# Emech_DevBoard_v2_0.net
KiCad netlist of a schematic drawn in EAGLE
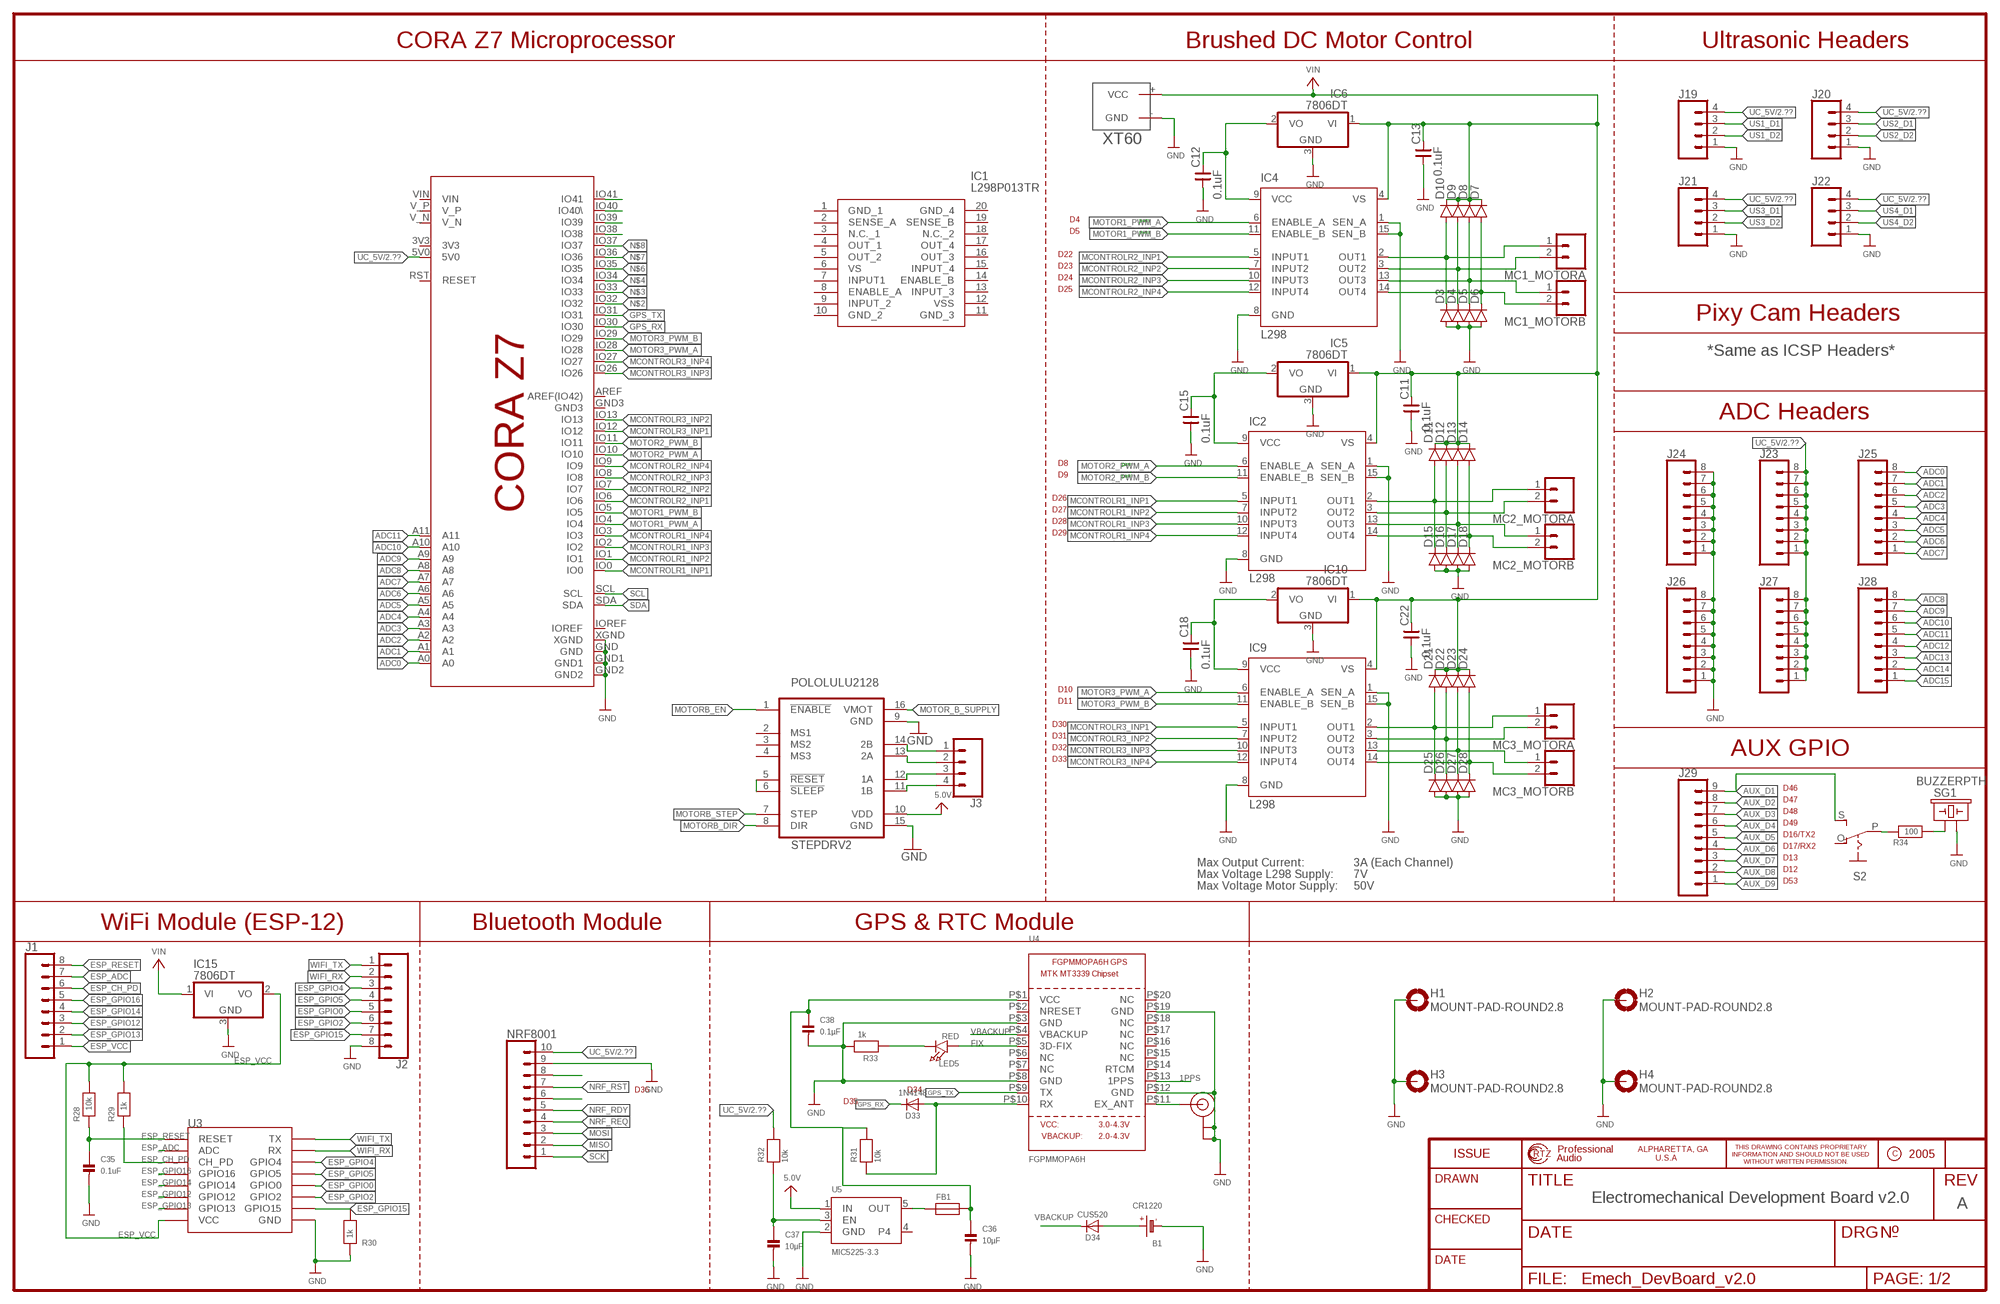
[diagram p0: schematic, sheet 1]
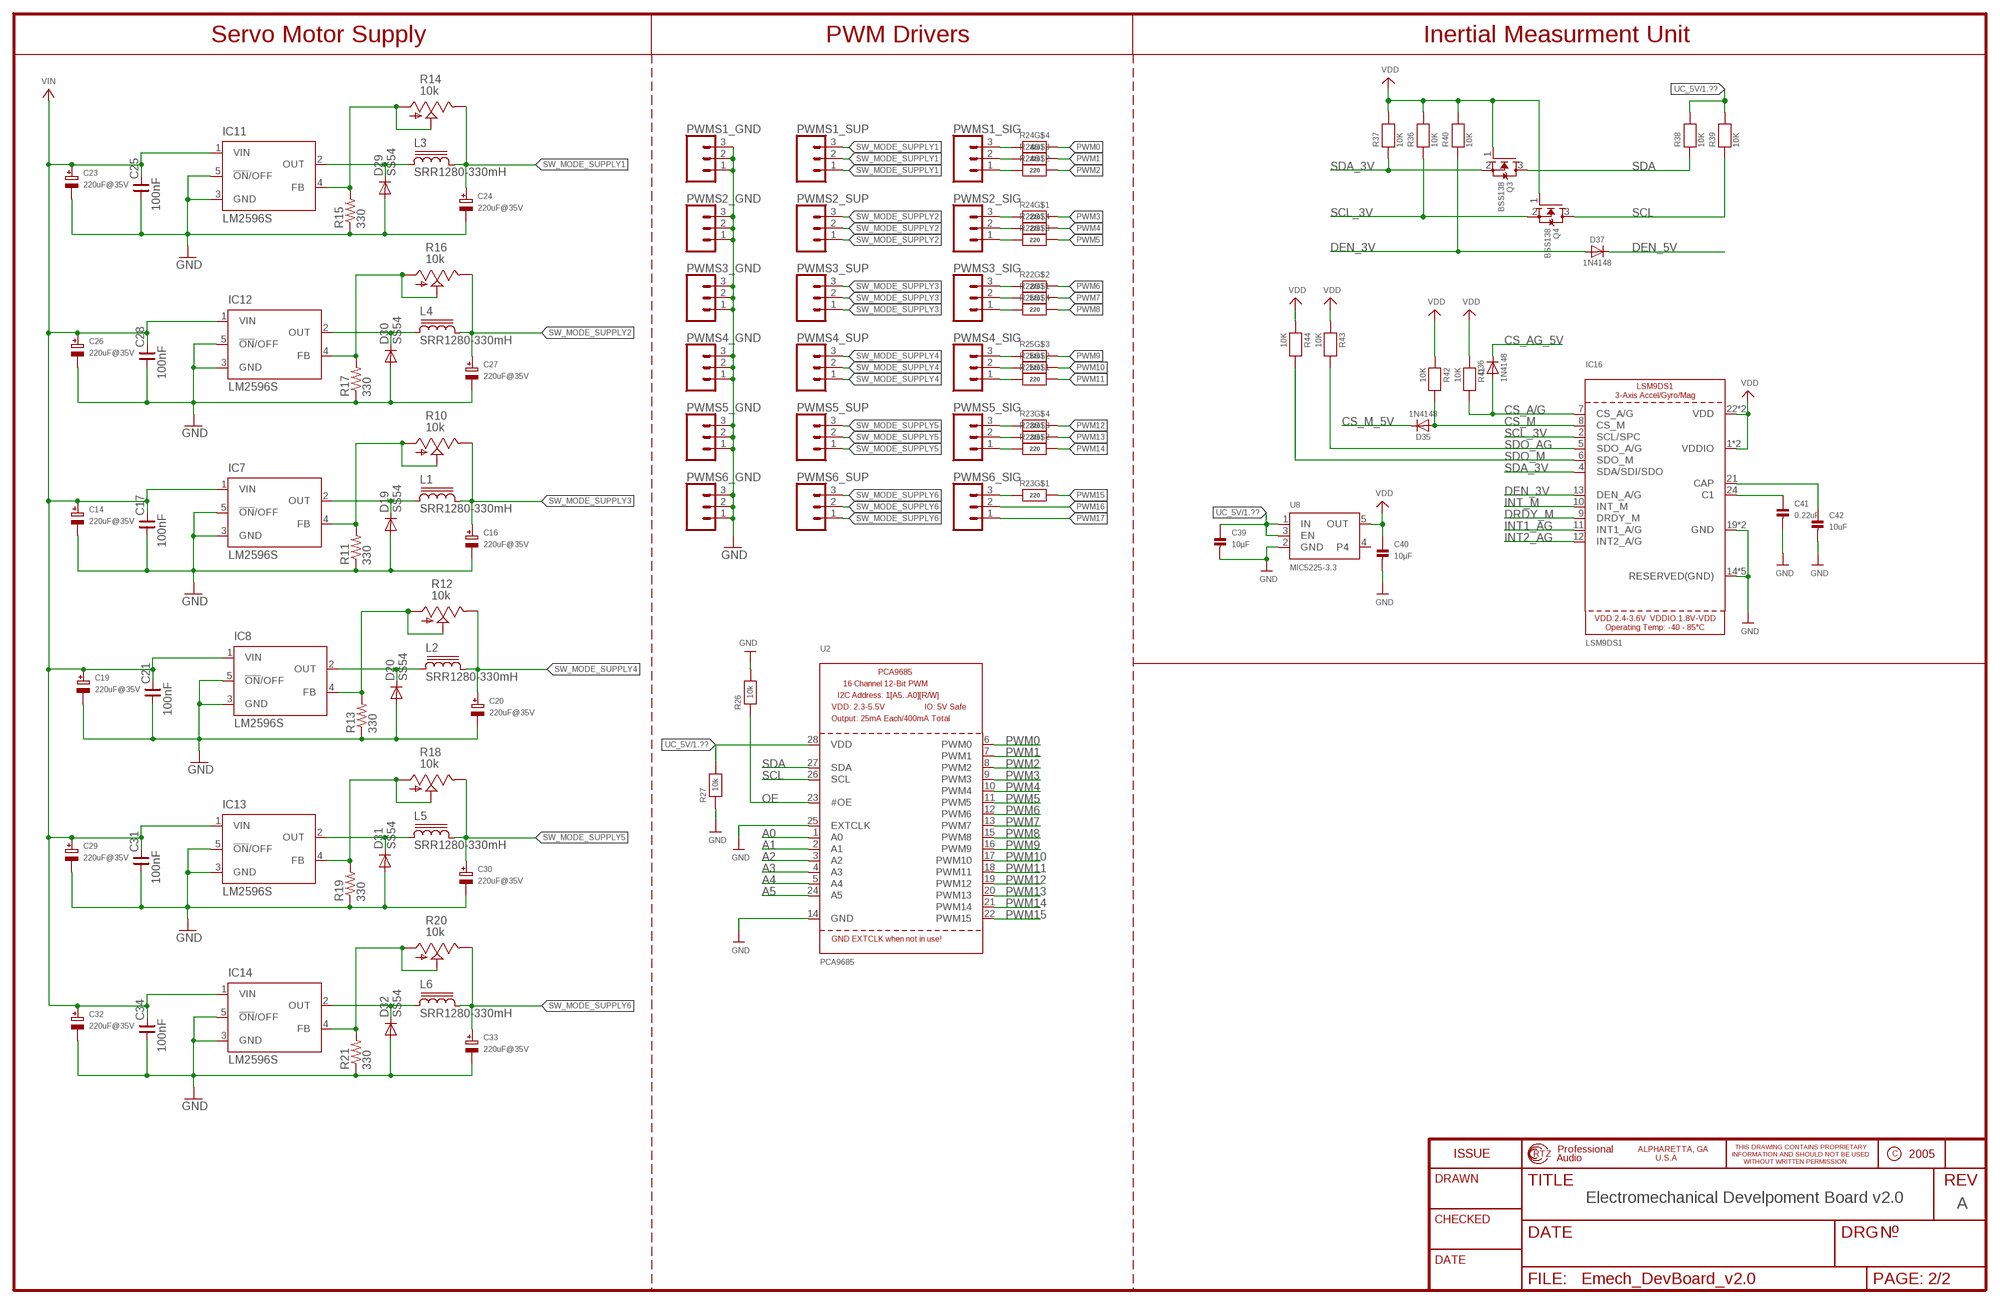
[diagram p1: schematic, sheet 2]

(export (version "E")
  (design (tool "Eeschema 10.0.6"))
  (components
    (comp (ref "C14")
      (value "220uF@35V")
      (footprint "eagle-import:PANASONIC_D")
      (libsource (lib "eagle-import") (part "CAP_ELECTROLYTICPANASONIC_D"))
    )
    (comp (ref "C16")
      (value "220uF@35V")
      (footprint "eagle-import:PANASONIC_D")
      (libsource (lib "eagle-import") (part "CAP_ELECTROLYTICPANASONIC_D"))
    )
    (comp (ref "C17")
      (value "100nF")
      (footprint "eagle-import:0603")
      (libsource (lib "eagle-import") (part "CNP-0603"))
    )
    (comp (ref "C19")
      (value "220uF@35V")
      (footprint "eagle-import:PANASONIC_D")
      (libsource (lib "eagle-import") (part "CAP_ELECTROLYTICPANASONIC_D"))
    )
    (comp (ref "C20")
      (value "220uF@35V")
      (footprint "eagle-import:PANASONIC_D")
      (libsource (lib "eagle-import") (part "CAP_ELECTROLYTICPANASONIC_D"))
    )
    (comp (ref "C21")
      (value "100nF")
      (footprint "eagle-import:0603")
      (libsource (lib "eagle-import") (part "CNP-0603"))
    )
    (comp (ref "C23")
      (value "220uF@35V")
      (footprint "eagle-import:PANASONIC_D")
      (libsource (lib "eagle-import") (part "CAP_ELECTROLYTICPANASONIC_D"))
    )
    (comp (ref "C24")
      (value "220uF@35V")
      (footprint "eagle-import:PANASONIC_D")
      (libsource (lib "eagle-import") (part "CAP_ELECTROLYTICPANASONIC_D"))
    )
    (comp (ref "C25")
      (value "100nF")
      (footprint "eagle-import:0603")
      (libsource (lib "eagle-import") (part "CNP-0603"))
    )
    (comp (ref "C26")
      (value "220uF@35V")
      (footprint "eagle-import:PANASONIC_D")
      (libsource (lib "eagle-import") (part "CAP_ELECTROLYTICPANASONIC_D"))
    )
    (comp (ref "C27")
      (value "220uF@35V")
      (footprint "eagle-import:PANASONIC_D")
      (libsource (lib "eagle-import") (part "CAP_ELECTROLYTICPANASONIC_D"))
    )
    (comp (ref "C28")
      (value "100nF")
      (footprint "eagle-import:0603")
      (libsource (lib "eagle-import") (part "CNP-0603"))
    )
    (comp (ref "C29")
      (value "220uF@35V")
      (footprint "eagle-import:PANASONIC_D")
      (libsource (lib "eagle-import") (part "CAP_ELECTROLYTICPANASONIC_D"))
    )
    (comp (ref "C30")
      (value "220uF@35V")
      (footprint "eagle-import:PANASONIC_D")
      (libsource (lib "eagle-import") (part "CAP_ELECTROLYTICPANASONIC_D"))
    )
    (comp (ref "C31")
      (value "100nF")
      (footprint "eagle-import:0603")
      (libsource (lib "eagle-import") (part "CNP-0603"))
    )
    (comp (ref "C32")
      (value "220uF@35V")
      (footprint "eagle-import:PANASONIC_D")
      (libsource (lib "eagle-import") (part "CAP_ELECTROLYTICPANASONIC_D"))
    )
    (comp (ref "C33")
      (value "220uF@35V")
      (footprint "eagle-import:PANASONIC_D")
      (libsource (lib "eagle-import") (part "CAP_ELECTROLYTICPANASONIC_D"))
    )
    (comp (ref "C34")
      (value "100nF")
      (footprint "eagle-import:0603")
      (libsource (lib "eagle-import") (part "CNP-0603"))
    )
    (comp (ref "C39")
      (value "10µF")
      (footprint "eagle-import:0603")
      (libsource (lib "eagle-import") (part "CAP_CERAMIC0603"))
    )
    (comp (ref "C40")
      (value "10µF")
      (footprint "eagle-import:0603")
      (libsource (lib "eagle-import") (part "CAP_CERAMIC0603"))
    )
    (comp (ref "C41")
      (value "0.22uF")
      (footprint "eagle-import:0603")
      (libsource (lib "eagle-import") (part "CAP_CERAMIC0603"))
    )
    (comp (ref "C42")
      (value "10uF")
      (footprint "eagle-import:0603")
      (libsource (lib "eagle-import") (part "CAP_CERAMIC0603"))
    )
    (comp (ref "D19")
      (value "SS54")
      (footprint "eagle-import:DO214AB")
      (fields (field (name "MF") "Fairchild") (field (name "MPN") "S3G"))
      (libsource (lib "eagle-import") (part "S3G"))
    )
    (comp (ref "D20")
      (value "SS54")
      (footprint "eagle-import:DO214AB")
      (fields (field (name "MF") "Fairchild") (field (name "MPN") "S3G"))
      (libsource (lib "eagle-import") (part "S3G"))
    )
    (comp (ref "D29")
      (value "SS54")
      (footprint "eagle-import:DO214AB")
      (fields (field (name "MF") "Fairchild") (field (name "MPN") "S3G"))
      (libsource (lib "eagle-import") (part "S3G"))
    )
    (comp (ref "D30")
      (value "SS54")
      (footprint "eagle-import:DO214AB")
      (fields (field (name "MF") "Fairchild") (field (name "MPN") "S3G"))
      (libsource (lib "eagle-import") (part "S3G"))
    )
    (comp (ref "D31")
      (value "SS54")
      (footprint "eagle-import:DO214AB")
      (fields (field (name "MF") "Fairchild") (field (name "MPN") "S3G"))
      (libsource (lib "eagle-import") (part "S3G"))
    )
    (comp (ref "D32")
      (value "SS54")
      (footprint "eagle-import:DO214AB")
      (fields (field (name "MF") "Fairchild") (field (name "MPN") "S3G"))
      (libsource (lib "eagle-import") (part "S3G"))
    )
    (comp (ref "D35")
      (value "1N4148")
      (footprint "eagle-import:SOD-323")
      (libsource (lib "eagle-import") (part "DIODESOD-323"))
    )
    (comp (ref "D36")
      (value "1N4148")
      (footprint "eagle-import:SOD-323")
      (libsource (lib "eagle-import") (part "DIODESOD-323"))
    )
    (comp (ref "D37")
      (value "1N4148")
      (footprint "eagle-import:SOD-323")
      (libsource (lib "eagle-import") (part "DIODESOD-323"))
    )
    (comp (ref "IC7")
      (value "LM2596S")
      (footprint "eagle-import:TO263-5")
      (fields (field (name "MF") "NATIONAL SEMICONDUCTOR") (field (name "MPN") "LM2596S-ADJ/NOPB"))
      (libsource (lib "eagle-import") (part "LM2596S"))
    )
    (comp (ref "IC8")
      (value "LM2596S")
      (footprint "eagle-import:TO263-5")
      (fields (field (name "MF") "NATIONAL SEMICONDUCTOR") (field (name "MPN") "LM2596S-ADJ/NOPB"))
      (libsource (lib "eagle-import") (part "LM2596S"))
    )
    (comp (ref "IC11")
      (value "LM2596S")
      (footprint "eagle-import:TO263-5")
      (fields (field (name "MF") "NATIONAL SEMICONDUCTOR") (field (name "MPN") "LM2596S-ADJ/NOPB"))
      (libsource (lib "eagle-import") (part "LM2596S"))
    )
    (comp (ref "IC12")
      (value "LM2596S")
      (footprint "eagle-import:TO263-5")
      (fields (field (name "MF") "NATIONAL SEMICONDUCTOR") (field (name "MPN") "LM2596S-ADJ/NOPB"))
      (libsource (lib "eagle-import") (part "LM2596S"))
    )
    (comp (ref "IC13")
      (value "LM2596S")
      (footprint "eagle-import:TO263-5")
      (fields (field (name "MF") "NATIONAL SEMICONDUCTOR") (field (name "MPN") "LM2596S-ADJ/NOPB"))
      (libsource (lib "eagle-import") (part "LM2596S"))
    )
    (comp (ref "IC14")
      (value "LM2596S")
      (footprint "eagle-import:TO263-5")
      (fields (field (name "MF") "NATIONAL SEMICONDUCTOR") (field (name "MPN") "LM2596S-ADJ/NOPB"))
      (libsource (lib "eagle-import") (part "LM2596S"))
    )
    (comp (ref "IC16")
      (value "LSM9DS1")
      (footprint "eagle-import:LGA24_3.5X3.1MM")
      (libsource (lib "eagle-import") (part "LSM9DS1"))
    )
    (comp (ref "L1")
      (value "SRR1280-330mH")
      (footprint "eagle-import:SRR1280")
      (libsource (lib "eagle-import") (part "SRR1280"))
    )
    (comp (ref "L2")
      (value "SRR1280-330mH")
      (footprint "eagle-import:SRR1280")
      (libsource (lib "eagle-import") (part "SRR1280"))
    )
    (comp (ref "L3")
      (value "SRR1280-330mH")
      (footprint "eagle-import:SRR1280")
      (libsource (lib "eagle-import") (part "SRR1280"))
    )
    (comp (ref "L4")
      (value "SRR1280-330mH")
      (footprint "eagle-import:SRR1280")
      (libsource (lib "eagle-import") (part "SRR1280"))
    )
    (comp (ref "L5")
      (value "SRR1280-330mH")
      (footprint "eagle-import:SRR1280")
      (libsource (lib "eagle-import") (part "SRR1280"))
    )
    (comp (ref "L6")
      (value "SRR1280-330mH")
      (footprint "eagle-import:SRR1280")
      (libsource (lib "eagle-import") (part "SRR1280"))
    )
    (comp (ref "PWMS1_GND")
      (value "CONN_03")
      (footprint "eagle-import:1X03")
      (libsource (lib "eagle-import") (part "CONN_03"))
    )
    (comp (ref "PWMS1_SIG")
      (value "CONN_03")
      (footprint "eagle-import:1X03")
      (libsource (lib "eagle-import") (part "CONN_03"))
    )
    (comp (ref "PWMS1_SUP")
      (value "CONN_03")
      (footprint "eagle-import:1X03")
      (libsource (lib "eagle-import") (part "CONN_03"))
    )
    (comp (ref "PWMS2_GND")
      (value "CONN_03")
      (footprint "eagle-import:1X03")
      (libsource (lib "eagle-import") (part "CONN_03"))
    )
    (comp (ref "PWMS2_SIG")
      (value "CONN_03")
      (footprint "eagle-import:1X03")
      (libsource (lib "eagle-import") (part "CONN_03"))
    )
    (comp (ref "PWMS2_SUP")
      (value "CONN_03")
      (footprint "eagle-import:1X03")
      (libsource (lib "eagle-import") (part "CONN_03"))
    )
    (comp (ref "PWMS3_GND")
      (value "CONN_03")
      (footprint "eagle-import:1X03")
      (libsource (lib "eagle-import") (part "CONN_03"))
    )
    (comp (ref "PWMS3_SIG")
      (value "CONN_03")
      (footprint "eagle-import:1X03")
      (libsource (lib "eagle-import") (part "CONN_03"))
    )
    (comp (ref "PWMS3_SUP")
      (value "CONN_03")
      (footprint "eagle-import:1X03")
      (libsource (lib "eagle-import") (part "CONN_03"))
    )
    (comp (ref "PWMS4_GND")
      (value "CONN_03")
      (footprint "eagle-import:1X03")
      (libsource (lib "eagle-import") (part "CONN_03"))
    )
    (comp (ref "PWMS4_SIG")
      (value "CONN_03")
      (footprint "eagle-import:1X03")
      (libsource (lib "eagle-import") (part "CONN_03"))
    )
    (comp (ref "PWMS4_SUP")
      (value "CONN_03")
      (footprint "eagle-import:1X03")
      (libsource (lib "eagle-import") (part "CONN_03"))
    )
    (comp (ref "PWMS5_GND")
      (value "CONN_03")
      (footprint "eagle-import:1X03")
      (libsource (lib "eagle-import") (part "CONN_03"))
    )
    (comp (ref "PWMS5_SIG")
      (value "CONN_03")
      (footprint "eagle-import:1X03")
      (libsource (lib "eagle-import") (part "CONN_03"))
    )
    (comp (ref "PWMS5_SUP")
      (value "CONN_03")
      (footprint "eagle-import:1X03")
      (libsource (lib "eagle-import") (part "CONN_03"))
    )
    (comp (ref "PWMS6_GND")
      (value "CONN_03")
      (footprint "eagle-import:1X03")
      (libsource (lib "eagle-import") (part "CONN_03"))
    )
    (comp (ref "PWMS6_SIG")
      (value "CONN_03")
      (footprint "eagle-import:1X03")
      (libsource (lib "eagle-import") (part "CONN_03"))
    )
    (comp (ref "PWMS6_SUP")
      (value "CONN_03")
      (footprint "eagle-import:1X03")
      (libsource (lib "eagle-import") (part "CONN_03"))
    )
    (comp (ref "Q3")
      (value "BSS138")
      (footprint "eagle-import:SOT23-WIDE")
      (libsource (lib "eagle-import") (part "MOSFET-NWIDE"))
    )
    (comp (ref "Q4")
      (value "BSS138")
      (footprint "eagle-import:SOT23-WIDE")
      (libsource (lib "eagle-import") (part "MOSFET-NWIDE"))
    )
    (comp (ref "R10")
      (value "10k")
      (footprint "eagle-import:S64W")
      (libsource (lib "eagle-import") (part "TRIM_US-S64W"))
    )
    (comp (ref "R11")
      (value "330")
      (footprint "eagle-import:R0603")
      (libsource (lib "eagle-import") (part "R-US_R0603"))
    )
    (comp (ref "R12")
      (value "10k")
      (footprint "eagle-import:S64W")
      (libsource (lib "eagle-import") (part "TRIM_US-S64W"))
    )
    (comp (ref "R13")
      (value "330")
      (footprint "eagle-import:R0603")
      (libsource (lib "eagle-import") (part "R-US_R0603"))
    )
    (comp (ref "R14")
      (value "10k")
      (footprint "eagle-import:S64W")
      (libsource (lib "eagle-import") (part "TRIM_US-S64W"))
    )
    (comp (ref "R15")
      (value "330")
      (footprint "eagle-import:R0603")
      (libsource (lib "eagle-import") (part "R-US_R0603"))
    )
    (comp (ref "R16")
      (value "10k")
      (footprint "eagle-import:S64W")
      (libsource (lib "eagle-import") (part "TRIM_US-S64W"))
    )
    (comp (ref "R17")
      (value "330")
      (footprint "eagle-import:R0603")
      (libsource (lib "eagle-import") (part "R-US_R0603"))
    )
    (comp (ref "R18")
      (value "10k")
      (footprint "eagle-import:S64W")
      (libsource (lib "eagle-import") (part "TRIM_US-S64W"))
    )
    (comp (ref "R19")
      (value "330")
      (footprint "eagle-import:R0603")
      (libsource (lib "eagle-import") (part "R-US_R0603"))
    )
    (comp (ref "R20")
      (value "10k")
      (footprint "eagle-import:S64W")
      (libsource (lib "eagle-import") (part "TRIM_US-S64W"))
    )
    (comp (ref "R21")
      (value "330")
      (footprint "eagle-import:R0603")
      (libsource (lib "eagle-import") (part "R-US_R0603"))
    )
    (comp (ref "R22")
      (value "220")
      (footprint "eagle-import:RESPACK_4X0603")
      (libsource (lib "eagle-import") (part "RESISTOR_4PACK"))
    )
    (comp (ref "R23")
      (value "220")
      (footprint "eagle-import:RESPACK_4X0603")
      (libsource (lib "eagle-import") (part "RESISTOR_4PACK"))
    )
    (comp (ref "R24")
      (value "220")
      (footprint "eagle-import:RESPACK_4X0603")
      (libsource (lib "eagle-import") (part "RESISTOR_4PACK"))
    )
    (comp (ref "R25")
      (value "220")
      (footprint "eagle-import:RESPACK_4X0603")
      (libsource (lib "eagle-import") (part "RESISTOR_4PACK"))
    )
    (comp (ref "R26")
      (value "10k")
      (footprint "eagle-import:0805")
      (libsource (lib "eagle-import") (part "RESISTOR0805"))
    )
    (comp (ref "R27")
      (value "10k")
      (footprint "eagle-import:0805")
      (libsource (lib "eagle-import") (part "RESISTOR0805"))
    )
    (comp (ref "R36")
      (value "10K")
      (footprint "eagle-import:0603")
      (libsource (lib "eagle-import") (part "RESISTOR0603"))
    )
    (comp (ref "R37")
      (value "10K")
      (footprint "eagle-import:0603")
      (libsource (lib "eagle-import") (part "RESISTOR0603"))
    )
    (comp (ref "R38")
      (value "10K")
      (footprint "eagle-import:0603")
      (libsource (lib "eagle-import") (part "RESISTOR0603"))
    )
    (comp (ref "R39")
      (value "10K")
      (footprint "eagle-import:0603")
      (libsource (lib "eagle-import") (part "RESISTOR0603"))
    )
    (comp (ref "R40")
      (value "10K")
      (footprint "eagle-import:0603")
      (libsource (lib "eagle-import") (part "RESISTOR0603"))
    )
    (comp (ref "R41")
      (value "10K")
      (footprint "eagle-import:0603")
      (libsource (lib "eagle-import") (part "RESISTOR0603"))
    )
    (comp (ref "R42")
      (value "10K")
      (footprint "eagle-import:0603")
      (libsource (lib "eagle-import") (part "RESISTOR0603"))
    )
    (comp (ref "R43")
      (value "10K")
      (footprint "eagle-import:0603")
      (libsource (lib "eagle-import") (part "RESISTOR0603"))
    )
    (comp (ref "R44")
      (value "10K")
      (footprint "eagle-import:0603")
      (libsource (lib "eagle-import") (part "RESISTOR0603"))
    )
    (comp (ref "U2")
      (value "PCA9685")
      (footprint "eagle-import:TSSOP28")
      (libsource (lib "eagle-import") (part "PCA9685"))
    )
    (comp (ref "U8")
      (value "MIC5225-3.3")
      (footprint "eagle-import:SOT23-5")
      (libsource (lib "eagle-import") (part "VREG_SOT23-5"))
    )
    (comp (ref "B1")
      (value "CR1220")
      (footprint "eagle-import:CR1220")
      (libsource (lib "eagle-import") (part "BATTERYCR1220_SMT"))
    )
    (comp (ref "C11")
      (value "0.1uF")
      (footprint "eagle-import:0603")
      (libsource (lib "eagle-import") (part "CNP-0603"))
    )
    (comp (ref "C12")
      (value "0.1uF")
      (footprint "eagle-import:0603")
      (libsource (lib "eagle-import") (part "CNP-0603"))
    )
    (comp (ref "C13")
      (value "0.1uF")
      (footprint "eagle-import:0603")
      (libsource (lib "eagle-import") (part "CNP-0603"))
    )
    (comp (ref "C15")
      (value "0.1uF")
      (footprint "eagle-import:0603")
      (libsource (lib "eagle-import") (part "CNP-0603"))
    )
    (comp (ref "C18")
      (value "0.1uF")
      (footprint "eagle-import:0603")
      (libsource (lib "eagle-import") (part "CNP-0603"))
    )
    (comp (ref "C22")
      (value "0.1uF")
      (footprint "eagle-import:0603")
      (libsource (lib "eagle-import") (part "CNP-0603"))
    )
    (comp (ref "C35")
      (value "0.1uF")
      (footprint "eagle-import:0805")
      (libsource (lib "eagle-import") (part "CAP_CERAMIC0805"))
    )
    (comp (ref "C36")
      (value "10µF")
      (footprint "eagle-import:0603")
      (libsource (lib "eagle-import") (part "CAP_CERAMIC0603"))
    )
    (comp (ref "C37")
      (value "10µF")
      (footprint "eagle-import:0603")
      (libsource (lib "eagle-import") (part "CAP_CERAMIC0603"))
    )
    (comp (ref "C38")
      (value "0.1µF")
      (footprint "eagle-import:0603")
      (libsource (lib "eagle-import") (part "CAP_CERAMIC0603"))
    )
    (comp (ref "D3")
      (value "SS24FSCT-ND")
      (footprint "eagle-import:DO-214AA")
      (libsource (lib "eagle-import") (part "DIODEDO214AA"))
    )
    (comp (ref "D4")
      (value "SS24FSCT-ND")
      (footprint "eagle-import:DO-214AA")
      (libsource (lib "eagle-import") (part "DIODEDO214AA"))
    )
    (comp (ref "D5")
      (value "SS24FSCT-ND")
      (footprint "eagle-import:DO-214AA")
      (libsource (lib "eagle-import") (part "DIODEDO214AA"))
    )
    (comp (ref "D6")
      (value "SS24FSCT-ND")
      (footprint "eagle-import:DO-214AA")
      (libsource (lib "eagle-import") (part "DIODEDO214AA"))
    )
    (comp (ref "D7")
      (value "SS24FSCT-ND")
      (footprint "eagle-import:DO-214AA")
      (libsource (lib "eagle-import") (part "DIODEDO214AA"))
    )
    (comp (ref "D8")
      (value "SS24FSCT-ND")
      (footprint "eagle-import:DO-214AA")
      (libsource (lib "eagle-import") (part "DIODEDO214AA"))
    )
    (comp (ref "D9")
      (value "SS24FSCT-ND")
      (footprint "eagle-import:DO-214AA")
      (libsource (lib "eagle-import") (part "DIODEDO214AA"))
    )
    (comp (ref "D10")
      (value "SS24FSCT-ND")
      (footprint "eagle-import:DO-214AA")
      (libsource (lib "eagle-import") (part "DIODEDO214AA"))
    )
    (comp (ref "D11")
      (value "SS24FSCT-ND")
      (footprint "eagle-import:DO-214AA")
      (libsource (lib "eagle-import") (part "DIODEDO214AA"))
    )
    (comp (ref "D12")
      (value "SS24FSCT-ND")
      (footprint "eagle-import:DO-214AA")
      (libsource (lib "eagle-import") (part "DIODEDO214AA"))
    )
    (comp (ref "D13")
      (value "SS24FSCT-ND")
      (footprint "eagle-import:DO-214AA")
      (libsource (lib "eagle-import") (part "DIODEDO214AA"))
    )
    (comp (ref "D14")
      (value "SS24FSCT-ND")
      (footprint "eagle-import:DO-214AA")
      (libsource (lib "eagle-import") (part "DIODEDO214AA"))
    )
    (comp (ref "D15")
      (value "SS24FSCT-ND")
      (footprint "eagle-import:DO-214AA")
      (libsource (lib "eagle-import") (part "DIODEDO214AA"))
    )
    (comp (ref "D16")
      (value "SS24FSCT-ND")
      (footprint "eagle-import:DO-214AA")
      (libsource (lib "eagle-import") (part "DIODEDO214AA"))
    )
    (comp (ref "D17")
      (value "SS24FSCT-ND")
      (footprint "eagle-import:DO-214AA")
      (libsource (lib "eagle-import") (part "DIODEDO214AA"))
    )
    (comp (ref "D18")
      (value "SS24FSCT-ND")
      (footprint "eagle-import:DO-214AA")
      (libsource (lib "eagle-import") (part "DIODEDO214AA"))
    )
    (comp (ref "D21")
      (value "SS24FSCT-ND")
      (footprint "eagle-import:DO-214AA")
      (libsource (lib "eagle-import") (part "DIODEDO214AA"))
    )
    (comp (ref "D22")
      (value "SS24FSCT-ND")
      (footprint "eagle-import:DO-214AA")
      (libsource (lib "eagle-import") (part "DIODEDO214AA"))
    )
    (comp (ref "D23")
      (value "SS24FSCT-ND")
      (footprint "eagle-import:DO-214AA")
      (libsource (lib "eagle-import") (part "DIODEDO214AA"))
    )
    (comp (ref "D24")
      (value "SS24FSCT-ND")
      (footprint "eagle-import:DO-214AA")
      (libsource (lib "eagle-import") (part "DIODEDO214AA"))
    )
    (comp (ref "D25")
      (value "SS24FSCT-ND")
      (footprint "eagle-import:DO-214AA")
      (libsource (lib "eagle-import") (part "DIODEDO214AA"))
    )
    (comp (ref "D26")
      (value "SS24FSCT-ND")
      (footprint "eagle-import:DO-214AA")
      (libsource (lib "eagle-import") (part "DIODEDO214AA"))
    )
    (comp (ref "D27")
      (value "SS24FSCT-ND")
      (footprint "eagle-import:DO-214AA")
      (libsource (lib "eagle-import") (part "DIODEDO214AA"))
    )
    (comp (ref "D28")
      (value "SS24FSCT-ND")
      (footprint "eagle-import:DO-214AA")
      (libsource (lib "eagle-import") (part "DIODEDO214AA"))
    )
    (comp (ref "D33")
      (value "1N4148")
      (footprint "eagle-import:SOD-323")
      (libsource (lib "eagle-import") (part "DIODESOD-323"))
    )
    (comp (ref "D34")
      (value "CUS520")
      (footprint "eagle-import:SOD-323")
      (libsource (lib "eagle-import") (part "DIODESOD-323"))
    )
    (comp (ref "FB1")
      (value "FERRITE")
      (footprint "eagle-import:0603")
      (libsource (lib "eagle-import") (part "FERRITE"))
    )
    (comp (ref "H1")
      (value "MOUNT-PAD-ROUND2.8")
      (footprint "eagle-import:2,8-PAD")
      (libsource (lib "eagle-import") (part "MOUNT-PAD-ROUND2.8"))
    )
    (comp (ref "H2")
      (value "MOUNT-PAD-ROUND2.8")
      (footprint "eagle-import:2,8-PAD")
      (libsource (lib "eagle-import") (part "MOUNT-PAD-ROUND2.8"))
    )
    (comp (ref "H3")
      (value "MOUNT-PAD-ROUND2.8")
      (footprint "eagle-import:2,8-PAD")
      (libsource (lib "eagle-import") (part "MOUNT-PAD-ROUND2.8"))
    )
    (comp (ref "H4")
      (value "MOUNT-PAD-ROUND2.8")
      (footprint "eagle-import:2,8-PAD")
      (libsource (lib "eagle-import") (part "MOUNT-PAD-ROUND2.8"))
    )
    (comp (ref "IC1")
      (value "L298P013TR")
      (footprint "eagle-import:SOIC127P1420X360-20N")
      (fields (field (name "MOUSER_PART_NUMBER") "511-L298P-TR") (field (name "RS_PART_NUMBER") "8805308P"))
      (libsource (lib "eagle-import") (part "L298P013TR"))
    )
    (comp (ref "IC2")
      (value "L298")
      (footprint "eagle-import:MULTIWATT-15")
      (fields (field (name "MPN") "L298N"))
      (libsource (lib "eagle-import") (part "L298"))
    )
    (comp (ref "IC4")
      (value "L298")
      (footprint "eagle-import:MULTIWATT-15")
      (fields (field (name "MPN") "L298N"))
      (libsource (lib "eagle-import") (part "L298"))
    )
    (comp (ref "IC5")
      (value "7806DT")
      (footprint "eagle-import:TO252")
      (libsource (lib "eagle-import") (part "78DT06"))
    )
    (comp (ref "IC6")
      (value "7806DT")
      (footprint "eagle-import:TO252")
      (libsource (lib "eagle-import") (part "78DT06"))
    )
    (comp (ref "IC9")
      (value "L298")
      (footprint "eagle-import:MULTIWATT-15")
      (fields (field (name "MPN") "L298N"))
      (libsource (lib "eagle-import") (part "L298"))
    )
    (comp (ref "IC10")
      (value "7806DT")
      (footprint "eagle-import:TO252")
      (libsource (lib "eagle-import") (part "78DT06"))
    )
    (comp (ref "IC15")
      (value "7806DT")
      (footprint "eagle-import:TO252")
      (libsource (lib "eagle-import") (part "78DT06"))
    )
    (comp (ref "J1")
      (value "CONN_08\"")
      (footprint "eagle-import:1X08")
      (libsource (lib "eagle-import") (part "CONN_08{dblquote}"))
    )
    (comp (ref "J2")
      (value "CONN_08\"")
      (footprint "eagle-import:1X08")
      (libsource (lib "eagle-import") (part "CONN_08{dblquote}"))
    )
    (comp (ref "J3")
      (value "CONN_04JST-PTH-VERT")
      (footprint "eagle-import:JST-4-PTH-VERT")
      (libsource (lib "eagle-import") (part "CONN_04JST-PTH-VERT"))
    )
    (comp (ref "J19")
      (value "CONN_04")
      (footprint "eagle-import:1X04")
      (libsource (lib "eagle-import") (part "SparkFun-Connectors_513_CONN_04"))
    )
    (comp (ref "J20")
      (value "CONN_04")
      (footprint "eagle-import:1X04")
      (libsource (lib "eagle-import") (part "SparkFun-Connectors_513_CONN_04"))
    )
    (comp (ref "J21")
      (value "CONN_04")
      (footprint "eagle-import:1X04")
      (libsource (lib "eagle-import") (part "SparkFun-Connectors_513_CONN_04"))
    )
    (comp (ref "J22")
      (value "CONN_04")
      (footprint "eagle-import:1X04")
      (libsource (lib "eagle-import") (part "SparkFun-Connectors_513_CONN_04"))
    )
    (comp (ref "J23")
      (value "CONN_08\"")
      (footprint "eagle-import:1X08")
      (libsource (lib "eagle-import") (part "CONN_08{dblquote}"))
    )
    (comp (ref "J24")
      (value "CONN_08\"")
      (footprint "eagle-import:1X08")
      (libsource (lib "eagle-import") (part "CONN_08{dblquote}"))
    )
    (comp (ref "J25")
      (value "CONN_08\"")
      (footprint "eagle-import:1X08")
      (libsource (lib "eagle-import") (part "CONN_08{dblquote}"))
    )
    (comp (ref "J26")
      (value "CONN_08\"")
      (footprint "eagle-import:1X08")
      (libsource (lib "eagle-import") (part "CONN_08{dblquote}"))
    )
    (comp (ref "J27")
      (value "CONN_08\"")
      (footprint "eagle-import:1X08")
      (libsource (lib "eagle-import") (part "CONN_08{dblquote}"))
    )
    (comp (ref "J28")
      (value "CONN_08\"")
      (footprint "eagle-import:1X08")
      (libsource (lib "eagle-import") (part "CONN_08{dblquote}"))
    )
    (comp (ref "J29")
      (value "CONN_09")
      (footprint "eagle-import:1X09")
      (libsource (lib "eagle-import") (part "CONN_09"))
    )
    (comp (ref "LED5")
      (value "RED")
      (footprint "eagle-import:CHIPLED_0805")
      (libsource (lib "eagle-import") (part "LED0805"))
    )
    (comp (ref "MC1_MOTORA")
      (value "CONN_025MM")
      (footprint "eagle-import:SCREWTERMINAL-5MM-2")
      (libsource (lib "eagle-import") (part "CONN_025MM"))
    )
    (comp (ref "MC1_MOTORB")
      (value "CONN_025MM")
      (footprint "eagle-import:SCREWTERMINAL-5MM-2")
      (libsource (lib "eagle-import") (part "CONN_025MM"))
    )
    (comp (ref "MC2_MOTORA")
      (value "CONN_025MM")
      (footprint "eagle-import:SCREWTERMINAL-5MM-2")
      (libsource (lib "eagle-import") (part "CONN_025MM"))
    )
    (comp (ref "MC2_MOTORB")
      (value "CONN_025MM")
      (footprint "eagle-import:SCREWTERMINAL-5MM-2")
      (libsource (lib "eagle-import") (part "CONN_025MM"))
    )
    (comp (ref "MC3_MOTORA")
      (value "CONN_025MM")
      (footprint "eagle-import:SCREWTERMINAL-5MM-2")
      (libsource (lib "eagle-import") (part "CONN_025MM"))
    )
    (comp (ref "MC3_MOTORB")
      (value "CONN_025MM")
      (footprint "eagle-import:SCREWTERMINAL-5MM-2")
      (libsource (lib "eagle-import") (part "CONN_025MM"))
    )
    (comp (ref "NRF8001")
      (value "CONN_10\"")
      (footprint "eagle-import:1X10")
      (libsource (lib "eagle-import") (part "CONN_10{dblquote}"))
    )
    (comp (ref "R28")
      (value "10k")
      (footprint "eagle-import:0805")
      (libsource (lib "eagle-import") (part "RESISTOR0805"))
    )
    (comp (ref "R29")
      (value "1k")
      (footprint "eagle-import:0805")
      (libsource (lib "eagle-import") (part "RESISTOR0805"))
    )
    (comp (ref "R30")
      (value "1k")
      (footprint "eagle-import:0805")
      (libsource (lib "eagle-import") (part "RESISTOR0805"))
    )
    (comp (ref "R31")
      (value "10k")
      (footprint "eagle-import:0603")
      (libsource (lib "eagle-import") (part "RESISTOR0603"))
    )
    (comp (ref "R32")
      (value "10k")
      (footprint "eagle-import:0603")
      (libsource (lib "eagle-import") (part "RESISTOR0603"))
    )
    (comp (ref "R33")
      (value "1k")
      (footprint "eagle-import:0603")
      (libsource (lib "eagle-import") (part "RESISTOR0603"))
    )
    (comp (ref "R34")
      (value "100")
      (footprint "eagle-import:0805")
      (libsource (lib "eagle-import") (part "RESISTOR0805"))
    )
    (comp (ref "S2")
      (value "EG1218S")
      (footprint "eagle-import:EG1218")
      (libsource (lib "eagle-import") (part "EG1218S"))
    )
    (comp (ref "SG1")
      (value "BUZZERPTH")
      (footprint "eagle-import:BUZZER-12MM")
      (libsource (lib "eagle-import") (part "BUZZERPTH"))
    )
    (comp (ref "STEPDRV2")
      (value "POLOLULU2128")
      (footprint "eagle-import:POLOLULU2128")
      (libsource (lib "eagle-import") (part "POLOLULU2128"))
    )
    (comp (ref "U$1")
      (value "CORA_Z7")
      (footprint "eagle-import:CORA_Z7_SHIELD")
      (libsource (lib "eagle-import") (part "CORA_Z7"))
    )
    (comp (ref "U$14")
      (value "XT60")
      (footprint "eagle-import:XT60")
      (libsource (lib "eagle-import") (part "XT60"))
    )
    (comp (ref "U$55")
      (value "U.FL")
      (footprint "eagle-import:U.FL")
      (libsource (lib "eagle-import") (part "U.FL"))
    )
    (comp (ref "U3")
      (value "ESP12")
      (footprint "eagle-import:ESP12")
      (libsource (lib "eagle-import") (part "ESP12"))
    )
    (comp (ref "U4")
      (value "FGPMMOPA6H")
      (footprint "eagle-import:FGPMMOPA6H")
      (libsource (lib "eagle-import") (part "GPS_FGPMMOPA6H"))
    )
    (comp (ref "U5")
      (value "MIC5225-3.3")
      (footprint "eagle-import:SOT23-5")
      (libsource (lib "eagle-import") (part "VREG_SOT23-5"))
    )
  )
  (nets
    (net (code "1") (name "1PPS") (class "Default")
      (node (ref "U4") (pin "P$13") (pinfunction "1PPS_P$13") (pintype "bidirectional"))
    )
    (net (code "2") (name "5.0V") (class "Default")
      (node (ref "STEPDRV2") (pin "10") (pinfunction "VDD_10") (pintype "power_in"))
      (node (ref "U5") (pin "1") (pinfunction "IN_1") (pintype "power_in"))
    )
    (net (code "3") (name "A0") (class "Default")
      (node (ref "U2") (pin "1") (pinfunction "A0_1") (pintype "bidirectional"))
    )
    (net (code "4") (name "A1") (class "Default")
      (node (ref "U2") (pin "2") (pinfunction "A1_2") (pintype "bidirectional"))
    )
    (net (code "5") (name "A2") (class "Default")
      (node (ref "U2") (pin "3") (pinfunction "A2_3") (pintype "bidirectional"))
    )
    (net (code "6") (name "A3") (class "Default")
      (node (ref "U2") (pin "4") (pinfunction "A3_4") (pintype "bidirectional"))
    )
    (net (code "7") (name "A4") (class "Default")
      (node (ref "U2") (pin "5") (pinfunction "A4_5") (pintype "bidirectional"))
    )
    (net (code "8") (name "A5") (class "Default")
      (node (ref "U2") (pin "24") (pinfunction "A5_24") (pintype "bidirectional"))
    )
    (net (code "9") (name "ADC0") (class "Default")
      (node (ref "J25") (pin "8") (pinfunction "8_8") (pintype "passive"))
      (node (ref "U$1") (pin "A0") (pinfunction "A0_A0") (pintype "bidirectional"))
    )
    (net (code "10") (name "ADC1") (class "Default")
      (node (ref "J25") (pin "7") (pinfunction "7_7") (pintype "passive"))
      (node (ref "U$1") (pin "A1") (pinfunction "A1_A1") (pintype "bidirectional"))
    )
    (net (code "11") (name "ADC2") (class "Default")
      (node (ref "J25") (pin "6") (pinfunction "6_6") (pintype "passive"))
      (node (ref "U$1") (pin "A2") (pinfunction "A2_A2") (pintype "bidirectional"))
    )
    (net (code "12") (name "ADC3") (class "Default")
      (node (ref "J25") (pin "5") (pinfunction "5_5") (pintype "passive"))
      (node (ref "U$1") (pin "A3") (pinfunction "A3_A3") (pintype "bidirectional"))
    )
    (net (code "13") (name "ADC4") (class "Default")
      (node (ref "J25") (pin "4") (pinfunction "4_4") (pintype "passive"))
      (node (ref "U$1") (pin "A4") (pinfunction "A4_A4") (pintype "bidirectional"))
    )
    (net (code "14") (name "ADC5") (class "Default")
      (node (ref "J25") (pin "3") (pinfunction "3_3") (pintype "passive"))
      (node (ref "U$1") (pin "A5") (pinfunction "A5_A5") (pintype "bidirectional"))
    )
    (net (code "15") (name "ADC6") (class "Default")
      (node (ref "J25") (pin "2") (pinfunction "2_2") (pintype "passive"))
      (node (ref "U$1") (pin "A6") (pinfunction "A6_A6") (pintype "bidirectional"))
    )
    (net (code "16") (name "ADC7") (class "Default")
      (node (ref "J25") (pin "1") (pinfunction "1_1") (pintype "passive"))
      (node (ref "U$1") (pin "A7") (pinfunction "A7_A7") (pintype "bidirectional"))
    )
    (net (code "17") (name "ADC8") (class "Default")
      (node (ref "J28") (pin "8") (pinfunction "8_8") (pintype "passive"))
      (node (ref "U$1") (pin "A8") (pinfunction "A8_A8") (pintype "bidirectional"))
    )
    (net (code "18") (name "ADC9") (class "Default")
      (node (ref "J28") (pin "7") (pinfunction "7_7") (pintype "passive"))
      (node (ref "U$1") (pin "A9") (pinfunction "A9_A9") (pintype "bidirectional"))
    )
    (net (code "19") (name "ADC10") (class "Default")
      (node (ref "J28") (pin "6") (pinfunction "6_6") (pintype "passive"))
      (node (ref "U$1") (pin "A10") (pinfunction "A10_A10") (pintype "bidirectional"))
    )
    (net (code "20") (name "ADC11") (class "Default")
      (node (ref "J28") (pin "5") (pinfunction "5_5") (pintype "passive"))
      (node (ref "U$1") (pin "A11") (pinfunction "A11_A11") (pintype "bidirectional"))
    )
    (net (code "21") (name "ADC12") (class "Default")
      (node (ref "J28") (pin "4") (pinfunction "4_4") (pintype "passive"))
    )
    (net (code "22") (name "ADC13") (class "Default")
      (node (ref "J28") (pin "3") (pinfunction "3_3") (pintype "passive"))
    )
    (net (code "23") (name "ADC14") (class "Default")
      (node (ref "J28") (pin "2") (pinfunction "2_2") (pintype "passive"))
    )
    (net (code "24") (name "ADC15") (class "Default")
      (node (ref "J28") (pin "1") (pinfunction "1_1") (pintype "passive"))
    )
    (net (code "25") (name "AUX_D1") (class "Default")
      (node (ref "J29") (pin "9") (pinfunction "9_9") (pintype "passive"))
      (node (ref "S2") (pin "S") (pinfunction "S_S") (pintype "passive"))
    )
    (net (code "26") (name "AUX_D2") (class "Default")
      (node (ref "J29") (pin "8") (pinfunction "8_8") (pintype "passive"))
    )
    (net (code "27") (name "AUX_D3") (class "Default")
      (node (ref "J29") (pin "7") (pinfunction "7_7") (pintype "passive"))
    )
    (net (code "28") (name "AUX_D4") (class "Default")
      (node (ref "J29") (pin "6") (pinfunction "6_6") (pintype "passive"))
    )
    (net (code "29") (name "AUX_D5") (class "Default")
      (node (ref "J29") (pin "5") (pinfunction "5_5") (pintype "passive"))
    )
    (net (code "30") (name "AUX_D6") (class "Default")
      (node (ref "J29") (pin "4") (pinfunction "4_4") (pintype "passive"))
    )
    (net (code "31") (name "AUX_D7") (class "Default")
      (node (ref "J29") (pin "3") (pinfunction "3_3") (pintype "passive"))
    )
    (net (code "32") (name "AUX_D8") (class "Default")
      (node (ref "J29") (pin "2") (pinfunction "2_2") (pintype "passive"))
    )
    (net (code "33") (name "AUX_D9") (class "Default")
      (node (ref "J29") (pin "1") (pinfunction "1_1") (pintype "passive"))
    )
    (net (code "34") (name "CS_AG_5V") (class "Default")
      (node (ref "D36") (pin "C") (pinfunction "C_C") (pintype "passive"))
    )
    (net (code "35") (name "CS_A{slash}G") (class "Default")
      (node (ref "D36") (pin "A") (pinfunction "A_A") (pintype "passive"))
      (node (ref "IC16") (pin "7") (pinfunction "CS_A/G_7") (pintype "bidirectional"))
      (node (ref "R41") (pin "2") (pinfunction "2_2") (pintype "passive"))
    )
    (net (code "36") (name "CS_M") (class "Default")
      (node (ref "D35") (pin "A") (pinfunction "A_A") (pintype "passive"))
      (node (ref "IC16") (pin "8") (pinfunction "CS_M_8") (pintype "bidirectional"))
      (node (ref "R42") (pin "2") (pinfunction "2_2") (pintype "passive"))
    )
    (net (code "37") (name "CS_M_5V") (class "Default")
      (node (ref "D35") (pin "C") (pinfunction "C_C") (pintype "passive"))
    )
    (net (code "38") (name "DEN_3V") (class "Default")
      (node (ref "D37") (pin "A") (pinfunction "A_A") (pintype "passive"))
      (node (ref "IC16") (pin "13") (pinfunction "DEN_A/G_13") (pintype "bidirectional"))
      (node (ref "R40") (pin "1") (pinfunction "1_1") (pintype "passive"))
    )
    (net (code "39") (name "DEN_5V") (class "Default")
      (node (ref "D37") (pin "C") (pinfunction "C_C") (pintype "passive"))
    )
    (net (code "40") (name "DRDY_M") (class "Default")
      (node (ref "IC16") (pin "9") (pinfunction "DRDY_M_9") (pintype "bidirectional"))
    )
    (net (code "41") (name "ESP_ADC") (class "Default")
      (node (ref "J1") (pin "7") (pinfunction "7_7") (pintype "passive"))
      (node (ref "U3") (pin "ADC") (pinfunction "ADC_ADC") (pintype "bidirectional"))
    )
    (net (code "42") (name "ESP_CH_PD") (class "Default")
      (node (ref "J1") (pin "6") (pinfunction "6_6") (pintype "passive"))
      (node (ref "R29") (pin "1") (pinfunction "1_1") (pintype "passive"))
      (node (ref "U3") (pin "CH_PD") (pinfunction "CH_PD_CH_PD") (pintype "bidirectional"))
    )
    (net (code "43") (name "ESP_GPIO0") (class "Default")
      (node (ref "J2") (pin "5") (pinfunction "5_5") (pintype "passive"))
      (node (ref "U3") (pin "GPIO0") (pinfunction "GPIO0_GPIO0") (pintype "bidirectional"))
    )
    (net (code "44") (name "ESP_GPIO2") (class "Default")
      (node (ref "J2") (pin "6") (pinfunction "6_6") (pintype "passive"))
      (node (ref "U3") (pin "GPIO2") (pinfunction "GPIO2_GPIO2") (pintype "bidirectional"))
    )
    (net (code "45") (name "ESP_GPIO4") (class "Default")
      (node (ref "J2") (pin "3") (pinfunction "3_3") (pintype "passive"))
      (node (ref "U3") (pin "GPIO4") (pinfunction "GPIO4_GPIO4") (pintype "bidirectional"))
    )
    (net (code "46") (name "ESP_GPIO5") (class "Default")
      (node (ref "J2") (pin "4") (pinfunction "4_4") (pintype "passive"))
      (node (ref "U3") (pin "GPIO5") (pinfunction "GPIO5_GPIO5") (pintype "bidirectional"))
    )
    (net (code "47") (name "ESP_GPIO12") (class "Default")
      (node (ref "J1") (pin "3") (pinfunction "3_3") (pintype "passive"))
      (node (ref "U3") (pin "GPIO12") (pinfunction "GPIO12_GPIO12") (pintype "bidirectional"))
    )
    (net (code "48") (name "ESP_GPIO13") (class "Default")
      (node (ref "J1") (pin "2") (pinfunction "2_2") (pintype "passive"))
      (node (ref "U3") (pin "GPIO13") (pinfunction "GPIO13_GPIO13") (pintype "bidirectional"))
    )
    (net (code "49") (name "ESP_GPIO14") (class "Default")
      (node (ref "J1") (pin "4") (pinfunction "4_4") (pintype "passive"))
      (node (ref "U3") (pin "GPIO14") (pinfunction "GPIO14_GPIO14") (pintype "bidirectional"))
    )
    (net (code "50") (name "ESP_GPIO15") (class "Default")
      (node (ref "J2") (pin "7") (pinfunction "7_7") (pintype "passive"))
      (node (ref "R30") (pin "2") (pinfunction "2_2") (pintype "passive"))
      (node (ref "U3") (pin "GPIO15") (pinfunction "GPIO15_GPIO15") (pintype "bidirectional"))
    )
    (net (code "51") (name "ESP_GPIO16") (class "Default")
      (node (ref "J1") (pin "5") (pinfunction "5_5") (pintype "passive"))
      (node (ref "U3") (pin "GPIO16") (pinfunction "GPIO16_GPIO16") (pintype "bidirectional"))
    )
    (net (code "52") (name "ESP_RESET") (class "Default")
      (node (ref "C35") (pin "1") (pinfunction "P$1_1") (pintype "passive"))
      (node (ref "J1") (pin "8") (pinfunction "8_8") (pintype "passive"))
      (node (ref "R28") (pin "1") (pinfunction "1_1") (pintype "passive"))
      (node (ref "U3") (pin "RESET") (pinfunction "RESET_RESET") (pintype "bidirectional"))
    )
    (net (code "53") (name "ESP_VCC") (class "Default")
      (node (ref "IC15") (pin "2") (pinfunction "VO_2") (pintype "passive"))
      (node (ref "J1") (pin "1") (pinfunction "1_1") (pintype "passive"))
      (node (ref "R28") (pin "2") (pinfunction "2_2") (pintype "passive"))
      (node (ref "R29") (pin "2") (pinfunction "2_2") (pintype "passive"))
      (node (ref "U3") (pin "VCC") (pinfunction "VCC_VCC") (pintype "bidirectional"))
    )
    (net (code "54") (name "FIX") (class "Default")
      (node (ref "LED5") (pin "A") (pinfunction "A_A") (pintype "passive"))
      (node (ref "U4") (pin "P$5") (pinfunction "3D-FIX_P$5") (pintype "bidirectional"))
    )
    (net (code "55") (name "GND") (class "Default")
      (node (ref "B1") (pin "-") (pinfunction "-_-") (pintype "passive"))
      (node (ref "C11") (pin "1") (pinfunction "1_1") (pintype "passive"))
      (node (ref "C12") (pin "1") (pinfunction "1_1") (pintype "passive"))
      (node (ref "C13") (pin "1") (pinfunction "1_1") (pintype "passive"))
      (node (ref "C14") (pin "-") (pinfunction "-_-") (pintype "passive"))
      (node (ref "C15") (pin "1") (pinfunction "1_1") (pintype "passive"))
      (node (ref "C16") (pin "-") (pinfunction "-_-") (pintype "passive"))
      (node (ref "C17") (pin "1") (pinfunction "1_1") (pintype "passive"))
      (node (ref "C18") (pin "1") (pinfunction "1_1") (pintype "passive"))
      (node (ref "C19") (pin "-") (pinfunction "-_-") (pintype "passive"))
      (node (ref "C20") (pin "-") (pinfunction "-_-") (pintype "passive"))
      (node (ref "C21") (pin "1") (pinfunction "1_1") (pintype "passive"))
      (node (ref "C22") (pin "1") (pinfunction "1_1") (pintype "passive"))
      (node (ref "C23") (pin "-") (pinfunction "-_-") (pintype "passive"))
      (node (ref "C24") (pin "-") (pinfunction "-_-") (pintype "passive"))
      (node (ref "C25") (pin "1") (pinfunction "1_1") (pintype "passive"))
      (node (ref "C26") (pin "-") (pinfunction "-_-") (pintype "passive"))
      (node (ref "C27") (pin "-") (pinfunction "-_-") (pintype "passive"))
      (node (ref "C28") (pin "1") (pinfunction "1_1") (pintype "passive"))
      (node (ref "C29") (pin "-") (pinfunction "-_-") (pintype "passive"))
      (node (ref "C30") (pin "-") (pinfunction "-_-") (pintype "passive"))
      (node (ref "C31") (pin "1") (pinfunction "1_1") (pintype "passive"))
      (node (ref "C32") (pin "-") (pinfunction "-_-") (pintype "passive"))
      (node (ref "C33") (pin "-") (pinfunction "-_-") (pintype "passive"))
      (node (ref "C34") (pin "1") (pinfunction "1_1") (pintype "passive"))
      (node (ref "C35") (pin "2") (pinfunction "P$2_2") (pintype "passive"))
      (node (ref "C36") (pin "2") (pinfunction "P$2_2") (pintype "passive"))
      (node (ref "C37") (pin "2") (pinfunction "P$2_2") (pintype "passive"))
      (node (ref "C38") (pin "2") (pinfunction "P$2_2") (pintype "passive"))
      (node (ref "C39") (pin "2") (pinfunction "P$2_2") (pintype "passive"))
      (node (ref "C40") (pin "2") (pinfunction "P$2_2") (pintype "passive"))
      (node (ref "C41") (pin "2") (pinfunction "P$2_2") (pintype "passive"))
      (node (ref "C42") (pin "2") (pinfunction "P$2_2") (pintype "passive"))
      (node (ref "D15") (pin "A") (pinfunction "A_A") (pintype "passive"))
      (node (ref "D16") (pin "A") (pinfunction "A_A") (pintype "passive"))
      (node (ref "D17") (pin "A") (pinfunction "A_A") (pintype "passive"))
      (node (ref "D18") (pin "A") (pinfunction "A_A") (pintype "passive"))
      (node (ref "D19") (pin "A") (pinfunction "A_A") (pintype "passive"))
      (node (ref "D20") (pin "A") (pinfunction "A_A") (pintype "passive"))
      (node (ref "D25") (pin "A") (pinfunction "A_A") (pintype "passive"))
      (node (ref "D26") (pin "A") (pinfunction "A_A") (pintype "passive"))
      (node (ref "D27") (pin "A") (pinfunction "A_A") (pintype "passive"))
      (node (ref "D28") (pin "A") (pinfunction "A_A") (pintype "passive"))
      (node (ref "D29") (pin "A") (pinfunction "A_A") (pintype "passive"))
      (node (ref "D3") (pin "A") (pinfunction "A_A") (pintype "passive"))
      (node (ref "D30") (pin "A") (pinfunction "A_A") (pintype "passive"))
      (node (ref "D31") (pin "A") (pinfunction "A_A") (pintype "passive"))
      (node (ref "D32") (pin "A") (pinfunction "A_A") (pintype "passive"))
      (node (ref "D4") (pin "A") (pinfunction "A_A") (pintype "passive"))
      (node (ref "D5") (pin "A") (pinfunction "A_A") (pintype "passive"))
      (node (ref "D6") (pin "A") (pinfunction "A_A") (pintype "passive"))
      (node (ref "H1") (pin "B2,8") (pinfunction "MOUNT_B2,8") (pintype "passive"))
      (node (ref "H2") (pin "B2,8") (pinfunction "MOUNT_B2,8") (pintype "passive"))
      (node (ref "H3") (pin "B2,8") (pinfunction "MOUNT_B2,8") (pintype "passive"))
      (node (ref "H4") (pin "B2,8") (pinfunction "MOUNT_B2,8") (pintype "passive"))
      (node (ref "IC10") (pin "3") (pinfunction "GND_3") (pintype "passive"))
      (node (ref "IC11") (pin "3") (pinfunction "GND_3") (pintype "power_in"))
      (node (ref "IC11") (pin "5") (pinfunction "~{ON}/OFF_5") (pintype "input"))
      (node (ref "IC12") (pin "3") (pinfunction "GND_3") (pintype "power_in"))
      (node (ref "IC12") (pin "5") (pinfunction "~{ON}/OFF_5") (pintype "input"))
      (node (ref "IC13") (pin "3") (pinfunction "GND_3") (pintype "power_in"))
      (node (ref "IC13") (pin "5") (pinfunction "~{ON}/OFF_5") (pintype "input"))
      (node (ref "IC14") (pin "3") (pinfunction "GND_3") (pintype "power_in"))
      (node (ref "IC14") (pin "5") (pinfunction "~{ON}/OFF_5") (pintype "input"))
      (node (ref "IC15") (pin "3") (pinfunction "GND_3") (pintype "passive"))
      (node (ref "IC16") (pin "14") (pinfunction "RESERVED(GND)_14") (pintype "power_in"))
      (node (ref "IC16") (pin "15") (pinfunction "RESERVED(GND)_15") (pintype "power_in"))
      (node (ref "IC16") (pin "16") (pinfunction "RESERVED(GND)_16") (pintype "power_in"))
      (node (ref "IC16") (pin "17") (pinfunction "RESERVED(GND)_17") (pintype "power_in"))
      (node (ref "IC16") (pin "18") (pinfunction "RESERVED(GND)_18") (pintype "power_in"))
      (node (ref "IC16") (pin "19") (pinfunction "GND_19") (pintype "power_in"))
      (node (ref "IC16") (pin "20") (pinfunction "GND_20") (pintype "power_in"))
      (node (ref "IC2") (pin "1") (pinfunction "SEN_A_1") (pintype "input"))
      (node (ref "IC2") (pin "15") (pinfunction "SEN_B_15") (pintype "input"))
      (node (ref "IC2") (pin "8") (pinfunction "GND_8") (pintype "power_in"))
      (node (ref "IC4") (pin "1") (pinfunction "SEN_A_1") (pintype "input"))
      (node (ref "IC4") (pin "15") (pinfunction "SEN_B_15") (pintype "input"))
      (node (ref "IC4") (pin "8") (pinfunction "GND_8") (pintype "power_in"))
      (node (ref "IC5") (pin "3") (pinfunction "GND_3") (pintype "passive"))
      (node (ref "IC6") (pin "3") (pinfunction "GND_3") (pintype "passive"))
      (node (ref "IC7") (pin "3") (pinfunction "GND_3") (pintype "power_in"))
      (node (ref "IC7") (pin "5") (pinfunction "~{ON}/OFF_5") (pintype "input"))
      (node (ref "IC8") (pin "3") (pinfunction "GND_3") (pintype "power_in"))
      (node (ref "IC8") (pin "5") (pinfunction "~{ON}/OFF_5") (pintype "input"))
      (node (ref "IC9") (pin "1") (pinfunction "SEN_A_1") (pintype "input"))
      (node (ref "IC9") (pin "15") (pinfunction "SEN_B_15") (pintype "input"))
      (node (ref "IC9") (pin "8") (pinfunction "GND_8") (pintype "power_in"))
      (node (ref "J19") (pin "1") (pinfunction "1_1") (pintype "passive"))
      (node (ref "J2") (pin "8") (pinfunction "8_8") (pintype "passive"))
      (node (ref "J20") (pin "1") (pinfunction "1_1") (pintype "passive"))
      (node (ref "J21") (pin "1") (pinfunction "1_1") (pintype "passive"))
      (node (ref "J22") (pin "1") (pinfunction "1_1") (pintype "passive"))
      (node (ref "J24") (pin "1") (pinfunction "1_1") (pintype "passive"))
      (node (ref "J24") (pin "2") (pinfunction "2_2") (pintype "passive"))
      (node (ref "J24") (pin "3") (pinfunction "3_3") (pintype "passive"))
      (node (ref "J24") (pin "4") (pinfunction "4_4") (pintype "passive"))
      (node (ref "J24") (pin "5") (pinfunction "5_5") (pintype "passive"))
      (node (ref "J24") (pin "6") (pinfunction "6_6") (pintype "passive"))
      (node (ref "J24") (pin "7") (pinfunction "7_7") (pintype "passive"))
      (node (ref "J24") (pin "8") (pinfunction "8_8") (pintype "passive"))
      (node (ref "J26") (pin "1") (pinfunction "1_1") (pintype "passive"))
      (node (ref "J26") (pin "2") (pinfunction "2_2") (pintype "passive"))
      (node (ref "J26") (pin "3") (pinfunction "3_3") (pintype "passive"))
      (node (ref "J26") (pin "4") (pinfunction "4_4") (pintype "passive"))
      (node (ref "J26") (pin "5") (pinfunction "5_5") (pintype "passive"))
      (node (ref "J26") (pin "6") (pinfunction "6_6") (pintype "passive"))
      (node (ref "J26") (pin "7") (pinfunction "7_7") (pintype "passive"))
      (node (ref "J26") (pin "8") (pinfunction "8_8") (pintype "passive"))
      (node (ref "NRF8001") (pin "9") (pinfunction "9_9") (pintype "passive"))
      (node (ref "PWMS1_GND") (pin "1") (pinfunction "1_1") (pintype "passive"))
      (node (ref "PWMS1_GND") (pin "2") (pinfunction "2_2") (pintype "passive"))
      (node (ref "PWMS1_GND") (pin "3") (pinfunction "3_3") (pintype "passive"))
      (node (ref "PWMS2_GND") (pin "1") (pinfunction "1_1") (pintype "passive"))
      (node (ref "PWMS2_GND") (pin "2") (pinfunction "2_2") (pintype "passive"))
      (node (ref "PWMS2_GND") (pin "3") (pinfunction "3_3") (pintype "passive"))
      (node (ref "PWMS3_GND") (pin "1") (pinfunction "1_1") (pintype "passive"))
      (node (ref "PWMS3_GND") (pin "2") (pinfunction "2_2") (pintype "passive"))
      (node (ref "PWMS3_GND") (pin "3") (pinfunction "3_3") (pintype "passive"))
      (node (ref "PWMS4_GND") (pin "1") (pinfunction "1_1") (pintype "passive"))
      (node (ref "PWMS4_GND") (pin "2") (pinfunction "2_2") (pintype "passive"))
      (node (ref "PWMS4_GND") (pin "3") (pinfunction "3_3") (pintype "passive"))
      (node (ref "PWMS5_GND") (pin "1") (pinfunction "1_1") (pintype "passive"))
      (node (ref "PWMS5_GND") (pin "2") (pinfunction "2_2") (pintype "passive"))
      (node (ref "PWMS5_GND") (pin "3") (pinfunction "3_3") (pintype "passive"))
      (node (ref "PWMS6_GND") (pin "1") (pinfunction "1_1") (pintype "passive"))
      (node (ref "PWMS6_GND") (pin "2") (pinfunction "2_2") (pintype "passive"))
      (node (ref "PWMS6_GND") (pin "3") (pinfunction "3_3") (pintype "passive"))
      (node (ref "R11") (pin "1") (pinfunction "1_1") (pintype "passive"))
      (node (ref "R13") (pin "1") (pinfunction "1_1") (pintype "passive"))
      (node (ref "R15") (pin "1") (pinfunction "1_1") (pintype "passive"))
      (node (ref "R17") (pin "1") (pinfunction "1_1") (pintype "passive"))
      (node (ref "R19") (pin "1") (pinfunction "1_1") (pintype "passive"))
      (node (ref "R21") (pin "1") (pinfunction "1_1") (pintype "passive"))
      (node (ref "R26") (pin "2") (pinfunction "2_2") (pintype "passive"))
      (node (ref "R27") (pin "1") (pinfunction "1_1") (pintype "passive"))
      (node (ref "R30") (pin "1") (pinfunction "1_1") (pintype "passive"))
      (node (ref "R33") (pin "2") (pinfunction "2_2") (pintype "passive"))
      (node (ref "SG1") (pin "-") (pinfunction "2_-") (pintype "passive"))
      (node (ref "STEPDRV2") (pin "15") (pinfunction "GND_15") (pintype "power_in"))
      (node (ref "STEPDRV2") (pin "9") (pinfunction "GND_9") (pintype "power_in"))
      (node (ref "U$1") (pin "GND") (pinfunction "GND_GND") (pintype "bidirectional"))
      (node (ref "U$1") (pin "GND1") (pinfunction "GND1_GND1") (pintype "bidirectional"))
      (node (ref "U$1") (pin "GND2") (pinfunction "GND2_GND2") (pintype "bidirectional"))
      (node (ref "U$1") (pin "XGND") (pinfunction "XGND_XGND") (pintype "bidirectional"))
      (node (ref "U$14") (pin "-") (pinfunction "GND_-") (pintype "bidirectional"))
      (node (ref "U$55") (pin "P$1") (pinfunction "GND_P$1") (pintype "bidirectional"))
      (node (ref "U$55") (pin "P$2") (pinfunction "GND_P$2") (pintype "bidirectional"))
      (node (ref "U2") (pin "14") (pinfunction "GND_14") (pintype "power_in"))
      (node (ref "U2") (pin "25") (pinfunction "EXTCLK_25") (pintype "input"))
      (node (ref "U3") (pin "GND") (pinfunction "GND_GND") (pintype "bidirectional"))
      (node (ref "U4") (pin "P$12") (pinfunction "GND_P$12") (pintype "bidirectional"))
      (node (ref "U4") (pin "P$19") (pinfunction "GND_P$19") (pintype "bidirectional"))
      (node (ref "U4") (pin "P$3") (pinfunction "GND_P$3") (pintype "bidirectional"))
      (node (ref "U4") (pin "P$8") (pinfunction "GND_P$8") (pintype "bidirectional"))
      (node (ref "U5") (pin "2") (pinfunction "GND_2") (pintype "power_in"))
      (node (ref "U8") (pin "2") (pinfunction "GND_2") (pintype "power_in"))
    )
    (net (code "56") (name "GPS_RX") (class "Default")
      (node (ref "D33") (pin "C") (pinfunction "C_C") (pintype "passive"))
      (node (ref "U$1") (pin "IO30") (pinfunction "IO30_IO30") (pintype "bidirectional"))
    )
    (net (code "57") (name "GPS_TX") (class "Default")
      (node (ref "U$1") (pin "IO31") (pinfunction "IO31_IO31") (pintype "bidirectional"))
      (node (ref "U4") (pin "P$9") (pinfunction "TX_P$9") (pintype "bidirectional"))
    )
    (net (code "58") (name "INT1_AG") (class "Default")
      (node (ref "IC16") (pin "11") (pinfunction "INT1_A/G_11") (pintype "bidirectional"))
    )
    (net (code "59") (name "INT2_AG") (class "Default")
      (node (ref "IC16") (pin "12") (pinfunction "INT2_A/G_12") (pintype "bidirectional"))
    )
    (net (code "60") (name "INT_M") (class "Default")
      (node (ref "IC16") (pin "10") (pinfunction "INT_M_10") (pintype "bidirectional"))
    )
    (net (code "61") (name "MCONTROLR1_INP1") (class "Default")
      (node (ref "IC2") (pin "5") (pinfunction "INPUT1_5") (pintype "input"))
      (node (ref "U$1") (pin "IO0") (pinfunction "IO0_IO0") (pintype "bidirectional"))
    )
    (net (code "62") (name "MCONTROLR1_INP2") (class "Default")
      (node (ref "IC2") (pin "7") (pinfunction "INPUT2_7") (pintype "input"))
      (node (ref "U$1") (pin "IO1") (pinfunction "IO1_IO1") (pintype "bidirectional"))
    )
    (net (code "63") (name "MCONTROLR1_INP3") (class "Default")
      (node (ref "IC2") (pin "10") (pinfunction "INPUT3_10") (pintype "input"))
      (node (ref "U$1") (pin "IO2") (pinfunction "IO2_IO2") (pintype "bidirectional"))
    )
    (net (code "64") (name "MCONTROLR1_INP4") (class "Default")
      (node (ref "IC2") (pin "12") (pinfunction "INPUT4_12") (pintype "input"))
      (node (ref "U$1") (pin "IO3") (pinfunction "IO3_IO3") (pintype "bidirectional"))
    )
    (net (code "65") (name "MCONTROLR2_INP1") (class "Default")
      (node (ref "IC4") (pin "5") (pinfunction "INPUT1_5") (pintype "input"))
      (node (ref "U$1") (pin "IO6") (pinfunction "IO6_IO6") (pintype "bidirectional"))
    )
    (net (code "66") (name "MCONTROLR2_INP2") (class "Default")
      (node (ref "IC4") (pin "7") (pinfunction "INPUT2_7") (pintype "input"))
      (node (ref "U$1") (pin "IO7") (pinfunction "IO7_IO7") (pintype "bidirectional"))
    )
    (net (code "67") (name "MCONTROLR2_INP3") (class "Default")
      (node (ref "IC4") (pin "10") (pinfunction "INPUT3_10") (pintype "input"))
      (node (ref "U$1") (pin "IO8") (pinfunction "IO8_IO8") (pintype "bidirectional"))
    )
    (net (code "68") (name "MCONTROLR2_INP4") (class "Default")
      (node (ref "IC4") (pin "12") (pinfunction "INPUT4_12") (pintype "input"))
      (node (ref "U$1") (pin "IO9") (pinfunction "IO9_IO9") (pintype "bidirectional"))
    )
    (net (code "69") (name "MCONTROLR3_INP1") (class "Default")
      (node (ref "IC9") (pin "5") (pinfunction "INPUT1_5") (pintype "input"))
      (node (ref "U$1") (pin "IO12") (pinfunction "IO12_IO12") (pintype "bidirectional"))
    )
    (net (code "70") (name "MCONTROLR3_INP2") (class "Default")
      (node (ref "IC9") (pin "7") (pinfunction "INPUT2_7") (pintype "input"))
      (node (ref "U$1") (pin "IO13") (pinfunction "IO13_IO13") (pintype "bidirectional"))
    )
    (net (code "71") (name "MCONTROLR3_INP3") (class "Default")
      (node (ref "IC9") (pin "10") (pinfunction "INPUT3_10") (pintype "input"))
      (node (ref "U$1") (pin "IO26") (pinfunction "IO26_IO26") (pintype "bidirectional"))
    )
    (net (code "72") (name "MCONTROLR3_INP4") (class "Default")
      (node (ref "IC9") (pin "12") (pinfunction "INPUT4_12") (pintype "input"))
      (node (ref "U$1") (pin "IO27") (pinfunction "IO27_IO27") (pintype "bidirectional"))
    )
    (net (code "73") (name "MISO") (class "Default")
      (node (ref "NRF8001") (pin "2") (pinfunction "2_2") (pintype "passive"))
    )
    (net (code "74") (name "MOSI") (class "Default")
      (node (ref "NRF8001") (pin "3") (pinfunction "3_3") (pintype "passive"))
    )
    (net (code "75") (name "MOTOR1_PWM_A") (class "Default")
      (node (ref "IC4") (pin "6") (pinfunction "ENABLE_A_6") (pintype "input"))
      (node (ref "U$1") (pin "IO4") (pinfunction "IO4_IO4") (pintype "bidirectional"))
    )
    (net (code "76") (name "MOTOR1_PWM_B") (class "Default")
      (node (ref "IC4") (pin "11") (pinfunction "ENABLE_B_11") (pintype "input"))
      (node (ref "U$1") (pin "IO5") (pinfunction "IO5_IO5") (pintype "bidirectional"))
    )
    (net (code "77") (name "MOTOR2_PWM_A") (class "Default")
      (node (ref "IC2") (pin "6") (pinfunction "ENABLE_A_6") (pintype "input"))
      (node (ref "U$1") (pin "IO10") (pinfunction "IO10_IO10") (pintype "bidirectional"))
    )
    (net (code "78") (name "MOTOR2_PWM_B") (class "Default")
      (node (ref "IC2") (pin "11") (pinfunction "ENABLE_B_11") (pintype "input"))
      (node (ref "U$1") (pin "IO11") (pinfunction "IO11_IO11") (pintype "bidirectional"))
    )
    (net (code "79") (name "MOTOR3_PWM_A") (class "Default")
      (node (ref "IC9") (pin "6") (pinfunction "ENABLE_A_6") (pintype "input"))
      (node (ref "U$1") (pin "IO28") (pinfunction "IO28_IO28") (pintype "bidirectional"))
    )
    (net (code "80") (name "MOTOR3_PWM_B") (class "Default")
      (node (ref "IC9") (pin "11") (pinfunction "ENABLE_B_11") (pintype "input"))
      (node (ref "U$1") (pin "IO29") (pinfunction "IO29_IO29") (pintype "bidirectional"))
    )
    (net (code "81") (name "MOTORB_DIR") (class "Default")
      (node (ref "STEPDRV2") (pin "8") (pinfunction "DIR_8") (pintype "input"))
    )
    (net (code "82") (name "MOTORB_EN") (class "Default")
      (node (ref "STEPDRV2") (pin "1") (pinfunction "~{ENABLE}_1") (pintype "input"))
    )
    (net (code "83") (name "MOTORB_STEP") (class "Default")
      (node (ref "STEPDRV2") (pin "7") (pinfunction "STEP_7") (pintype "input"))
    )
    (net (code "84") (name "MOTOR_B_SUPPLY") (class "Default")
      (node (ref "STEPDRV2") (pin "16") (pinfunction "VMOT_16") (pintype "power_in"))
    )
    (net (code "85") (name "N$2") (class "Default")
      (node (ref "U$1") (pin "IO32") (pinfunction "IO32_IO32") (pintype "bidirectional"))
    )
    (net (code "86") (name "N$3") (class "Default")
      (node (ref "U$1") (pin "IO33") (pinfunction "IO33_IO33") (pintype "bidirectional"))
    )
    (net (code "87") (name "N$4") (class "Default")
      (node (ref "U$1") (pin "IO34") (pinfunction "IO34_IO34") (pintype "bidirectional"))
    )
    (net (code "88") (name "N$6") (class "Default")
      (node (ref "U$1") (pin "IO35") (pinfunction "IO35_IO35") (pintype "bidirectional"))
    )
    (net (code "89") (name "N$7") (class "Default")
      (node (ref "U$1") (pin "IO36") (pinfunction "IO36_IO36") (pintype "bidirectional"))
    )
    (net (code "90") (name "N$8") (class "Default")
      (node (ref "U$1") (pin "IO37") (pinfunction "IO37_IO37") (pintype "bidirectional"))
    )
    (net (code "91") (name "NRF_RDY") (class "Default")
      (node (ref "NRF8001") (pin "5") (pinfunction "5_5") (pintype "passive"))
    )
    (net (code "92") (name "NRF_REQ") (class "Default")
      (node (ref "NRF8001") (pin "4") (pinfunction "4_4") (pintype "passive"))
    )
    (net (code "93") (name "NRF_RST") (class "Default")
      (node (ref "NRF8001") (pin "7") (pinfunction "7_7") (pintype "passive"))
    )
    (net (code "94") (name "Net-(B1-+-Pad+$1)") (class "Default")
      (node (ref "B1") (pin "+$1") (pinfunction "+_+$1") (pintype "passive"))
      (node (ref "B1") (pin "+$2") (pinfunction "+_+$2") (pintype "passive"))
      (node (ref "D34") (pin "A") (pinfunction "A_A") (pintype "passive"))
    )
    (net (code "95") (name "Net-(C36-P$1)") (class "Default")
      (node (ref "C36") (pin "1") (pinfunction "P$1_1") (pintype "passive"))
      (node (ref "C38") (pin "1") (pinfunction "P$1_1") (pintype "passive"))
      (node (ref "FB1") (pin "2") (pinfunction "P$2_2") (pintype "bidirectional"))
      (node (ref "R31") (pin "2") (pinfunction "2_2") (pintype "passive"))
      (node (ref "U4") (pin "P$1") (pinfunction "VCC_P$1") (pintype "bidirectional"))
    )
    (net (code "96") (name "Net-(C37-P$1)") (class "Default")
      (node (ref "C37") (pin "1") (pinfunction "P$1_1") (pintype "passive"))
      (node (ref "R32") (pin "1") (pinfunction "1_1") (pintype "passive"))
      (node (ref "U5") (pin "3") (pinfunction "EN_3") (pintype "input"))
    )
    (net (code "97") (name "Net-(C41-P$1)") (class "Default")
      (node (ref "C41") (pin "1") (pinfunction "P$1_1") (pintype "passive"))
      (node (ref "IC16") (pin "24") (pinfunction "C1_24") (pintype "bidirectional"))
    )
    (net (code "98") (name "Net-(C42-P$1)") (class "Default")
      (node (ref "C42") (pin "1") (pinfunction "P$1_1") (pintype "passive"))
      (node (ref "IC16") (pin "21") (pinfunction "CAP_21") (pintype "bidirectional"))
    )
    (net (code "99") (name "Net-(FB1-P$1)") (class "Default")
      (node (ref "FB1") (pin "1") (pinfunction "P$1_1") (pintype "bidirectional"))
      (node (ref "U5") (pin "5") (pinfunction "OUT_5") (pintype "power_in"))
    )
    (net (code "100") (name "Net-(IC2-OUT1)") (class "Default")
      (node (ref "D11") (pin "A") (pinfunction "A_A") (pintype "passive"))
      (node (ref "D15") (pin "C") (pinfunction "C_C") (pintype "passive"))
      (node (ref "IC2") (pin "2") (pinfunction "OUT1_2") (pintype "output"))
      (node (ref "MC2_MOTORA") (pin "1") (pinfunction "1_1") (pintype "passive"))
    )
    (net (code "101") (name "Net-(IC2-OUT2)") (class "Default")
      (node (ref "D12") (pin "A") (pinfunction "A_A") (pintype "passive"))
      (node (ref "D16") (pin "C") (pinfunction "C_C") (pintype "passive"))
      (node (ref "IC2") (pin "3") (pinfunction "OUT2_3") (pintype "output"))
      (node (ref "MC2_MOTORA") (pin "2") (pinfunction "2_2") (pintype "passive"))
    )
    (net (code "102") (name "Net-(IC2-OUT3)") (class "Default")
      (node (ref "D13") (pin "A") (pinfunction "A_A") (pintype "passive"))
      (node (ref "D17") (pin "C") (pinfunction "C_C") (pintype "passive"))
      (node (ref "IC2") (pin "13") (pinfunction "OUT3_13") (pintype "output"))
      (node (ref "MC2_MOTORB") (pin "1") (pinfunction "1_1") (pintype "passive"))
    )
    (net (code "103") (name "Net-(IC2-OUT4)") (class "Default")
      (node (ref "D14") (pin "A") (pinfunction "A_A") (pintype "passive"))
      (node (ref "D18") (pin "C") (pinfunction "C_C") (pintype "passive"))
      (node (ref "IC2") (pin "14") (pinfunction "OUT4_14") (pintype "output"))
      (node (ref "MC2_MOTORB") (pin "2") (pinfunction "2_2") (pintype "passive"))
    )
    (net (code "104") (name "Net-(IC2-VCC)") (class "Default")
      (node (ref "C15") (pin "2") (pinfunction "2_2") (pintype "passive"))
      (node (ref "IC2") (pin "9") (pinfunction "VCC_9") (pintype "power_in"))
      (node (ref "IC5") (pin "2") (pinfunction "VO_2") (pintype "passive"))
    )
    (net (code "105") (name "Net-(IC4-OUT1)") (class "Default")
      (node (ref "D10") (pin "A") (pinfunction "A_A") (pintype "passive"))
      (node (ref "D3") (pin "C") (pinfunction "C_C") (pintype "passive"))
      (node (ref "IC4") (pin "2") (pinfunction "OUT1_2") (pintype "output"))
      (node (ref "MC1_MOTORA") (pin "1") (pinfunction "1_1") (pintype "passive"))
    )
    (net (code "106") (name "Net-(IC4-OUT2)") (class "Default")
      (node (ref "D4") (pin "C") (pinfunction "C_C") (pintype "passive"))
      (node (ref "D9") (pin "A") (pinfunction "A_A") (pintype "passive"))
      (node (ref "IC4") (pin "3") (pinfunction "OUT2_3") (pintype "output"))
      (node (ref "MC1_MOTORA") (pin "2") (pinfunction "2_2") (pintype "passive"))
    )
    (net (code "107") (name "Net-(IC4-OUT3)") (class "Default")
      (node (ref "D5") (pin "C") (pinfunction "C_C") (pintype "passive"))
      (node (ref "D8") (pin "A") (pinfunction "A_A") (pintype "passive"))
      (node (ref "IC4") (pin "13") (pinfunction "OUT3_13") (pintype "output"))
      (node (ref "MC1_MOTORB") (pin "1") (pinfunction "1_1") (pintype "passive"))
    )
    (net (code "108") (name "Net-(IC4-OUT4)") (class "Default")
      (node (ref "D6") (pin "C") (pinfunction "C_C") (pintype "passive"))
      (node (ref "D7") (pin "A") (pinfunction "A_A") (pintype "passive"))
      (node (ref "IC4") (pin "14") (pinfunction "OUT4_14") (pintype "output"))
      (node (ref "MC1_MOTORB") (pin "2") (pinfunction "2_2") (pintype "passive"))
    )
    (net (code "109") (name "Net-(IC4-VCC)") (class "Default")
      (node (ref "C12") (pin "2") (pinfunction "2_2") (pintype "passive"))
      (node (ref "IC4") (pin "9") (pinfunction "VCC_9") (pintype "power_in"))
      (node (ref "IC6") (pin "2") (pinfunction "VO_2") (pintype "passive"))
    )
    (net (code "110") (name "Net-(IC7-FB)") (class "Default")
      (node (ref "IC7") (pin "4") (pinfunction "FB_4") (pintype "input"))
      (node (ref "R10") (pin "A") (pinfunction "A_A") (pintype "passive"))
      (node (ref "R10") (pin "S") (pinfunction "S_S") (pintype "passive"))
      (node (ref "R11") (pin "2") (pinfunction "2_2") (pintype "passive"))
    )
    (net (code "111") (name "Net-(IC7-OUT)") (class "Default")
      (node (ref "D19") (pin "C") (pinfunction "C_C") (pintype "passive"))
      (node (ref "IC7") (pin "2") (pinfunction "OUT_2") (pintype "output"))
      (node (ref "L1") (pin "1") (pinfunction "1_1") (pintype "passive"))
    )
    (net (code "112") (name "Net-(IC8-FB)") (class "Default")
      (node (ref "IC8") (pin "4") (pinfunction "FB_4") (pintype "input"))
      (node (ref "R12") (pin "A") (pinfunction "A_A") (pintype "passive"))
      (node (ref "R12") (pin "S") (pinfunction "S_S") (pintype "passive"))
      (node (ref "R13") (pin "2") (pinfunction "2_2") (pintype "passive"))
    )
    (net (code "113") (name "Net-(IC8-OUT)") (class "Default")
      (node (ref "D20") (pin "C") (pinfunction "C_C") (pintype "passive"))
      (node (ref "IC8") (pin "2") (pinfunction "OUT_2") (pintype "output"))
      (node (ref "L2") (pin "1") (pinfunction "1_1") (pintype "passive"))
    )
    (net (code "114") (name "Net-(IC9-OUT1)") (class "Default")
      (node (ref "D21") (pin "A") (pinfunction "A_A") (pintype "passive"))
      (node (ref "D25") (pin "C") (pinfunction "C_C") (pintype "passive"))
      (node (ref "IC9") (pin "2") (pinfunction "OUT1_2") (pintype "output"))
      (node (ref "MC3_MOTORA") (pin "1") (pinfunction "1_1") (pintype "passive"))
    )
    (net (code "115") (name "Net-(IC9-OUT2)") (class "Default")
      (node (ref "D22") (pin "A") (pinfunction "A_A") (pintype "passive"))
      (node (ref "D26") (pin "C") (pinfunction "C_C") (pintype "passive"))
      (node (ref "IC9") (pin "3") (pinfunction "OUT2_3") (pintype "output"))
      (node (ref "MC3_MOTORA") (pin "2") (pinfunction "2_2") (pintype "passive"))
    )
    (net (code "116") (name "Net-(IC9-OUT3)") (class "Default")
      (node (ref "D23") (pin "A") (pinfunction "A_A") (pintype "passive"))
      (node (ref "D27") (pin "C") (pinfunction "C_C") (pintype "passive"))
      (node (ref "IC9") (pin "13") (pinfunction "OUT3_13") (pintype "output"))
      (node (ref "MC3_MOTORB") (pin "1") (pinfunction "1_1") (pintype "passive"))
    )
    (net (code "117") (name "Net-(IC9-OUT4)") (class "Default")
      (node (ref "D24") (pin "A") (pinfunction "A_A") (pintype "passive"))
      (node (ref "D28") (pin "C") (pinfunction "C_C") (pintype "passive"))
      (node (ref "IC9") (pin "14") (pinfunction "OUT4_14") (pintype "output"))
      (node (ref "MC3_MOTORB") (pin "2") (pinfunction "2_2") (pintype "passive"))
    )
    (net (code "118") (name "Net-(IC10-VO)") (class "Default")
      (node (ref "C18") (pin "2") (pinfunction "2_2") (pintype "passive"))
      (node (ref "IC10") (pin "2") (pinfunction "VO_2") (pintype "passive"))
      (node (ref "IC9") (pin "9") (pinfunction "VCC_9") (pintype "power_in"))
    )
    (net (code "119") (name "Net-(IC11-FB)") (class "Default")
      (node (ref "IC11") (pin "4") (pinfunction "FB_4") (pintype "input"))
      (node (ref "R14") (pin "A") (pinfunction "A_A") (pintype "passive"))
      (node (ref "R14") (pin "S") (pinfunction "S_S") (pintype "passive"))
      (node (ref "R15") (pin "2") (pinfunction "2_2") (pintype "passive"))
    )
    (net (code "120") (name "Net-(IC11-OUT)") (class "Default")
      (node (ref "D29") (pin "C") (pinfunction "C_C") (pintype "passive"))
      (node (ref "IC11") (pin "2") (pinfunction "OUT_2") (pintype "output"))
      (node (ref "L3") (pin "1") (pinfunction "1_1") (pintype "passive"))
    )
    (net (code "121") (name "Net-(IC12-FB)") (class "Default")
      (node (ref "IC12") (pin "4") (pinfunction "FB_4") (pintype "input"))
      (node (ref "R16") (pin "A") (pinfunction "A_A") (pintype "passive"))
      (node (ref "R16") (pin "S") (pinfunction "S_S") (pintype "passive"))
      (node (ref "R17") (pin "2") (pinfunction "2_2") (pintype "passive"))
    )
    (net (code "122") (name "Net-(IC12-OUT)") (class "Default")
      (node (ref "D30") (pin "C") (pinfunction "C_C") (pintype "passive"))
      (node (ref "IC12") (pin "2") (pinfunction "OUT_2") (pintype "output"))
      (node (ref "L4") (pin "1") (pinfunction "1_1") (pintype "passive"))
    )
    (net (code "123") (name "Net-(IC13-FB)") (class "Default")
      (node (ref "IC13") (pin "4") (pinfunction "FB_4") (pintype "input"))
      (node (ref "R18") (pin "A") (pinfunction "A_A") (pintype "passive"))
      (node (ref "R18") (pin "S") (pinfunction "S_S") (pintype "passive"))
      (node (ref "R19") (pin "2") (pinfunction "2_2") (pintype "passive"))
    )
    (net (code "124") (name "Net-(IC13-OUT)") (class "Default")
      (node (ref "D31") (pin "C") (pinfunction "C_C") (pintype "passive"))
      (node (ref "IC13") (pin "2") (pinfunction "OUT_2") (pintype "output"))
      (node (ref "L5") (pin "1") (pinfunction "1_1") (pintype "passive"))
    )
    (net (code "125") (name "Net-(IC14-FB)") (class "Default")
      (node (ref "IC14") (pin "4") (pinfunction "FB_4") (pintype "input"))
      (node (ref "R20") (pin "A") (pinfunction "A_A") (pintype "passive"))
      (node (ref "R20") (pin "S") (pinfunction "S_S") (pintype "passive"))
      (node (ref "R21") (pin "2") (pinfunction "2_2") (pintype "passive"))
    )
    (net (code "126") (name "Net-(IC14-OUT)") (class "Default")
      (node (ref "D32") (pin "C") (pinfunction "C_C") (pintype "passive"))
      (node (ref "IC14") (pin "2") (pinfunction "OUT_2") (pintype "output"))
      (node (ref "L6") (pin "1") (pinfunction "1_1") (pintype "passive"))
    )
    (net (code "127") (name "Net-(LED5-PadC)") (class "Default")
      (node (ref "LED5") (pin "C") (pinfunction "C_C") (pintype "passive"))
      (node (ref "R33") (pin "1") (pinfunction "1_1") (pintype "passive"))
    )
    (net (code "128") (name "Net-(PWMS2_SIG-Pad3)") (class "Default")
      (node (ref "PWMS2_SIG") (pin "3") (pinfunction "3_3") (pintype "passive"))
      (node (ref "R24") (pin "1") (pinfunction "1_1") (pintype "passive"))
    )
    (net (code "129") (name "Net-(PWMS3_SIG-Pad2)") (class "Default")
      (node (ref "PWMS3_SIG") (pin "2") (pinfunction "2_2") (pintype "passive"))
      (node (ref "R22") (pin "1") (pinfunction "1_1") (pintype "passive"))
    )
    (net (code "130") (name "Net-(PWMS4_SIG-Pad1)") (class "Default")
      (node (ref "PWMS4_SIG") (pin "1") (pinfunction "1_1") (pintype "passive"))
      (node (ref "R25") (pin "1") (pinfunction "1_1") (pintype "passive"))
    )
    (net (code "131") (name "Net-(PWMS6_SIG-Pad3)") (class "Default")
      (node (ref "PWMS6_SIG") (pin "3") (pinfunction "3_3") (pintype "passive"))
      (node (ref "R23") (pin "1") (pinfunction "1_1") (pintype "passive"))
    )
    (net (code "132") (name "Net-(R22B-1)") (class "Default")
      (node (ref "PWMS3_SIG") (pin "3") (pinfunction "3_3") (pintype "passive"))
      (node (ref "R22") (pin "2") (pinfunction "1_2") (pintype "passive"))
    )
    (net (code "133") (name "Net-(R22C-1)") (class "Default")
      (node (ref "PWMS2_SIG") (pin "1") (pinfunction "1_1") (pintype "passive"))
      (node (ref "R22") (pin "3") (pinfunction "1_3") (pintype "passive"))
    )
    (net (code "134") (name "Net-(R22D-1)") (class "Default")
      (node (ref "PWMS2_SIG") (pin "2") (pinfunction "2_2") (pintype "passive"))
      (node (ref "R22") (pin "4") (pinfunction "1_4") (pintype "passive"))
    )
    (net (code "135") (name "Net-(R23B-1)") (class "Default")
      (node (ref "PWMS5_SIG") (pin "1") (pinfunction "1_1") (pintype "passive"))
      (node (ref "R23") (pin "2") (pinfunction "1_2") (pintype "passive"))
    )
    (net (code "136") (name "Net-(R23C-1)") (class "Default")
      (node (ref "PWMS5_SIG") (pin "2") (pinfunction "2_2") (pintype "passive"))
      (node (ref "R23") (pin "3") (pinfunction "1_3") (pintype "passive"))
    )
    (net (code "137") (name "Net-(R23D-1)") (class "Default")
      (node (ref "PWMS5_SIG") (pin "3") (pinfunction "3_3") (pintype "passive"))
      (node (ref "R23") (pin "4") (pinfunction "1_4") (pintype "passive"))
    )
    (net (code "138") (name "Net-(R24B-1)") (class "Default")
      (node (ref "PWMS1_SIG") (pin "1") (pinfunction "1_1") (pintype "passive"))
      (node (ref "R24") (pin "2") (pinfunction "1_2") (pintype "passive"))
    )
    (net (code "139") (name "Net-(R24C-1)") (class "Default")
      (node (ref "PWMS1_SIG") (pin "2") (pinfunction "2_2") (pintype "passive"))
      (node (ref "R24") (pin "3") (pinfunction "1_3") (pintype "passive"))
    )
    (net (code "140") (name "Net-(R24D-1)") (class "Default")
      (node (ref "PWMS1_SIG") (pin "3") (pinfunction "3_3") (pintype "passive"))
      (node (ref "R24") (pin "4") (pinfunction "1_4") (pintype "passive"))
    )
    (net (code "141") (name "Net-(R25B-1)") (class "Default")
      (node (ref "PWMS4_SIG") (pin "2") (pinfunction "2_2") (pintype "passive"))
      (node (ref "R25") (pin "2") (pinfunction "1_2") (pintype "passive"))
    )
    (net (code "142") (name "Net-(R25C-1)") (class "Default")
      (node (ref "PWMS4_SIG") (pin "3") (pinfunction "3_3") (pintype "passive"))
      (node (ref "R25") (pin "3") (pinfunction "1_3") (pintype "passive"))
    )
    (net (code "143") (name "Net-(R25D-1)") (class "Default")
      (node (ref "PWMS3_SIG") (pin "1") (pinfunction "1_1") (pintype "passive"))
      (node (ref "R25") (pin "4") (pinfunction "1_4") (pintype "passive"))
    )
    (net (code "144") (name "Net-(R34-Pad2)") (class "Default")
      (node (ref "R34") (pin "2") (pinfunction "2_2") (pintype "passive"))
      (node (ref "S2") (pin "P") (pinfunction "P_P") (pintype "passive"))
    )
    (net (code "145") (name "Net-(SG1-1)") (class "Default")
      (node (ref "R34") (pin "1") (pinfunction "1_1") (pintype "passive"))
      (node (ref "SG1") (pin "+") (pinfunction "1_+") (pintype "passive"))
    )
    (net (code "146") (name "Net-(STEPDRV2-1A)") (class "Default")
      (node (ref "J3") (pin "3") (pinfunction "3_3") (pintype "passive"))
      (node (ref "STEPDRV2") (pin "12") (pinfunction "1A_12") (pintype "output"))
    )
    (net (code "147") (name "Net-(STEPDRV2-1B)") (class "Default")
      (node (ref "J3") (pin "4") (pinfunction "4_4") (pintype "passive"))
      (node (ref "STEPDRV2") (pin "11") (pinfunction "1B_11") (pintype "output"))
    )
    (net (code "148") (name "Net-(STEPDRV2-2A)") (class "Default")
      (node (ref "J3") (pin "2") (pinfunction "2_2") (pintype "passive"))
      (node (ref "STEPDRV2") (pin "13") (pinfunction "2A_13") (pintype "output"))
    )
    (net (code "149") (name "Net-(STEPDRV2-2B)") (class "Default")
      (node (ref "J3") (pin "1") (pinfunction "1_1") (pintype "passive"))
      (node (ref "STEPDRV2") (pin "14") (pinfunction "2B_14") (pintype "output"))
    )
    (net (code "150") (name "Net-(STEPDRV2-~{RESET})") (class "Default")
      (node (ref "STEPDRV2") (pin "5") (pinfunction "~{RESET}_5") (pintype "input"))
      (node (ref "STEPDRV2") (pin "6") (pinfunction "~{SLEEP}_6") (pintype "input"))
    )
    (net (code "151") (name "Net-(U$55-SIGNAL)") (class "Default")
      (node (ref "U$55") (pin "P$3") (pinfunction "SIGNAL_P$3") (pintype "bidirectional"))
      (node (ref "U4") (pin "P$11") (pinfunction "EX_ANT_P$11") (pintype "bidirectional"))
    )
    (net (code "152") (name "Net-(U4-RX)") (class "Default")
      (node (ref "D33") (pin "A") (pinfunction "A_A") (pintype "passive"))
      (node (ref "R31") (pin "1") (pinfunction "1_1") (pintype "passive"))
      (node (ref "U4") (pin "P$10") (pinfunction "RX_P$10") (pintype "bidirectional"))
    )
    (net (code "153") (name "OE") (class "Default")
      (node (ref "R26") (pin "1") (pinfunction "1_1") (pintype "passive"))
      (node (ref "U2") (pin "23") (pinfunction "#OE_23") (pintype "input"))
    )
    (net (code "154") (name "PWM0") (class "Default")
      (node (ref "R24") (pin "5") (pinfunction "2_5") (pintype "passive"))
      (node (ref "U2") (pin "6") (pinfunction "PWM0_6") (pintype "output"))
    )
    (net (code "155") (name "PWM1") (class "Default")
      (node (ref "R24") (pin "6") (pinfunction "2_6") (pintype "passive"))
      (node (ref "U2") (pin "7") (pinfunction "PWM1_7") (pintype "output"))
    )
    (net (code "156") (name "PWM2") (class "Default")
      (node (ref "R24") (pin "7") (pinfunction "2_7") (pintype "passive"))
      (node (ref "U2") (pin "8") (pinfunction "PWM2_8") (pintype "output"))
    )
    (net (code "157") (name "PWM3") (class "Default")
      (node (ref "R24") (pin "8") (pinfunction "2_8") (pintype "passive"))
      (node (ref "U2") (pin "9") (pinfunction "PWM3_9") (pintype "output"))
    )
    (net (code "158") (name "PWM4") (class "Default")
      (node (ref "R22") (pin "5") (pinfunction "2_5") (pintype "passive"))
      (node (ref "U2") (pin "10") (pinfunction "PWM4_10") (pintype "output"))
    )
    (net (code "159") (name "PWM5") (class "Default")
      (node (ref "R22") (pin "6") (pinfunction "2_6") (pintype "passive"))
      (node (ref "U2") (pin "11") (pinfunction "PWM5_11") (pintype "output"))
    )
    (net (code "160") (name "PWM6") (class "Default")
      (node (ref "R22") (pin "7") (pinfunction "2_7") (pintype "passive"))
      (node (ref "U2") (pin "12") (pinfunction "PWM6_12") (pintype "output"))
    )
    (net (code "161") (name "PWM7") (class "Default")
      (node (ref "R22") (pin "8") (pinfunction "2_8") (pintype "passive"))
      (node (ref "U2") (pin "13") (pinfunction "PWM7_13") (pintype "output"))
    )
    (net (code "162") (name "PWM8") (class "Default")
      (node (ref "R25") (pin "5") (pinfunction "2_5") (pintype "passive"))
      (node (ref "U2") (pin "15") (pinfunction "PWM8_15") (pintype "output"))
    )
    (net (code "163") (name "PWM9") (class "Default")
      (node (ref "R25") (pin "6") (pinfunction "2_6") (pintype "passive"))
      (node (ref "U2") (pin "16") (pinfunction "PWM9_16") (pintype "output"))
    )
    (net (code "164") (name "PWM10") (class "Default")
      (node (ref "R25") (pin "7") (pinfunction "2_7") (pintype "passive"))
      (node (ref "U2") (pin "17") (pinfunction "PWM10_17") (pintype "output"))
    )
    (net (code "165") (name "PWM11") (class "Default")
      (node (ref "R25") (pin "8") (pinfunction "2_8") (pintype "passive"))
      (node (ref "U2") (pin "18") (pinfunction "PWM11_18") (pintype "output"))
    )
    (net (code "166") (name "PWM12") (class "Default")
      (node (ref "R23") (pin "5") (pinfunction "2_5") (pintype "passive"))
      (node (ref "U2") (pin "19") (pinfunction "PWM12_19") (pintype "output"))
    )
    (net (code "167") (name "PWM13") (class "Default")
      (node (ref "R23") (pin "6") (pinfunction "2_6") (pintype "passive"))
      (node (ref "U2") (pin "20") (pinfunction "PWM13_20") (pintype "output"))
    )
    (net (code "168") (name "PWM14") (class "Default")
      (node (ref "R23") (pin "7") (pinfunction "2_7") (pintype "passive"))
      (node (ref "U2") (pin "21") (pinfunction "PWM14_21") (pintype "output"))
    )
    (net (code "169") (name "PWM15") (class "Default")
      (node (ref "R23") (pin "8") (pinfunction "2_8") (pintype "passive"))
      (node (ref "U2") (pin "22") (pinfunction "PWM15_22") (pintype "output"))
    )
    (net (code "170") (name "PWM16") (class "Default")
      (node (ref "PWMS6_SIG") (pin "2") (pinfunction "2_2") (pintype "passive"))
    )
    (net (code "171") (name "PWM17") (class "Default")
      (node (ref "PWMS6_SIG") (pin "1") (pinfunction "1_1") (pintype "passive"))
    )
    (net (code "172") (name "SCK") (class "Default")
      (node (ref "NRF8001") (pin "1") (pinfunction "1_1") (pintype "passive"))
    )
    (net (code "173") (name "SCL") (class "Default")
      (node (ref "Q4") (pin "3") (pinfunction "D_3") (pintype "bidirectional"))
      (node (ref "R39") (pin "1") (pinfunction "1_1") (pintype "passive"))
      (node (ref "U$1") (pin "SCL") (pinfunction "SCL_SCL") (pintype "bidirectional"))
      (node (ref "U2") (pin "26") (pinfunction "SCL_26") (pintype "bidirectional"))
    )
    (net (code "174") (name "SCL_3V") (class "Default")
      (node (ref "IC16") (pin "2") (pinfunction "SCL/SPC_2") (pintype "bidirectional"))
      (node (ref "Q4") (pin "2") (pinfunction "S_2") (pintype "bidirectional"))
      (node (ref "R36") (pin "1") (pinfunction "1_1") (pintype "passive"))
    )
    (net (code "175") (name "SDA") (class "Default")
      (node (ref "Q3") (pin "3") (pinfunction "D_3") (pintype "bidirectional"))
      (node (ref "R38") (pin "1") (pinfunction "1_1") (pintype "passive"))
      (node (ref "U$1") (pin "SDA") (pinfunction "SDA_SDA") (pintype "bidirectional"))
      (node (ref "U2") (pin "27") (pinfunction "SDA_27") (pintype "bidirectional"))
    )
    (net (code "176") (name "SDA_3V") (class "Default")
      (node (ref "IC16") (pin "4") (pinfunction "SDA/SDI/SDO_4") (pintype "bidirectional"))
      (node (ref "Q3") (pin "2") (pinfunction "S_2") (pintype "bidirectional"))
      (node (ref "R37") (pin "1") (pinfunction "1_1") (pintype "passive"))
    )
    (net (code "177") (name "SDO_AG") (class "Default")
      (node (ref "IC16") (pin "5") (pinfunction "SDO_A/G_5") (pintype "bidirectional"))
      (node (ref "R43") (pin "2") (pinfunction "2_2") (pintype "passive"))
    )
    (net (code "178") (name "SDO_M") (class "Default")
      (node (ref "IC16") (pin "6") (pinfunction "SDO_M_6") (pintype "bidirectional"))
      (node (ref "R44") (pin "2") (pinfunction "2_2") (pintype "passive"))
    )
    (net (code "179") (name "SW_MODE_SUPPLY1") (class "Default")
      (node (ref "C24") (pin "+") (pinfunction "+_+") (pintype "passive"))
      (node (ref "L3") (pin "2") (pinfunction "2_2") (pintype "passive"))
      (node (ref "PWMS1_SUP") (pin "1") (pinfunction "1_1") (pintype "passive"))
      (node (ref "PWMS1_SUP") (pin "2") (pinfunction "2_2") (pintype "passive"))
      (node (ref "PWMS1_SUP") (pin "3") (pinfunction "3_3") (pintype "passive"))
      (node (ref "R14") (pin "E") (pinfunction "E_E") (pintype "passive"))
    )
    (net (code "180") (name "SW_MODE_SUPPLY2") (class "Default")
      (node (ref "C27") (pin "+") (pinfunction "+_+") (pintype "passive"))
      (node (ref "L4") (pin "2") (pinfunction "2_2") (pintype "passive"))
      (node (ref "PWMS2_SUP") (pin "1") (pinfunction "1_1") (pintype "passive"))
      (node (ref "PWMS2_SUP") (pin "2") (pinfunction "2_2") (pintype "passive"))
      (node (ref "PWMS2_SUP") (pin "3") (pinfunction "3_3") (pintype "passive"))
      (node (ref "R16") (pin "E") (pinfunction "E_E") (pintype "passive"))
    )
    (net (code "181") (name "SW_MODE_SUPPLY3") (class "Default")
      (node (ref "C16") (pin "+") (pinfunction "+_+") (pintype "passive"))
      (node (ref "L1") (pin "2") (pinfunction "2_2") (pintype "passive"))
      (node (ref "PWMS3_SUP") (pin "1") (pinfunction "1_1") (pintype "passive"))
      (node (ref "PWMS3_SUP") (pin "2") (pinfunction "2_2") (pintype "passive"))
      (node (ref "PWMS3_SUP") (pin "3") (pinfunction "3_3") (pintype "passive"))
      (node (ref "R10") (pin "E") (pinfunction "E_E") (pintype "passive"))
    )
    (net (code "182") (name "SW_MODE_SUPPLY4") (class "Default")
      (node (ref "C20") (pin "+") (pinfunction "+_+") (pintype "passive"))
      (node (ref "L2") (pin "2") (pinfunction "2_2") (pintype "passive"))
      (node (ref "PWMS4_SUP") (pin "1") (pinfunction "1_1") (pintype "passive"))
      (node (ref "PWMS4_SUP") (pin "2") (pinfunction "2_2") (pintype "passive"))
      (node (ref "PWMS4_SUP") (pin "3") (pinfunction "3_3") (pintype "passive"))
      (node (ref "R12") (pin "E") (pinfunction "E_E") (pintype "passive"))
    )
    (net (code "183") (name "SW_MODE_SUPPLY5") (class "Default")
      (node (ref "C30") (pin "+") (pinfunction "+_+") (pintype "passive"))
      (node (ref "L5") (pin "2") (pinfunction "2_2") (pintype "passive"))
      (node (ref "PWMS5_SUP") (pin "1") (pinfunction "1_1") (pintype "passive"))
      (node (ref "PWMS5_SUP") (pin "2") (pinfunction "2_2") (pintype "passive"))
      (node (ref "PWMS5_SUP") (pin "3") (pinfunction "3_3") (pintype "passive"))
      (node (ref "R18") (pin "E") (pinfunction "E_E") (pintype "passive"))
    )
    (net (code "184") (name "SW_MODE_SUPPLY6") (class "Default")
      (node (ref "C33") (pin "+") (pinfunction "+_+") (pintype "passive"))
      (node (ref "L6") (pin "2") (pinfunction "2_2") (pintype "passive"))
      (node (ref "PWMS6_SUP") (pin "1") (pinfunction "1_1") (pintype "passive"))
      (node (ref "PWMS6_SUP") (pin "2") (pinfunction "2_2") (pintype "passive"))
      (node (ref "PWMS6_SUP") (pin "3") (pinfunction "3_3") (pintype "passive"))
      (node (ref "R20") (pin "E") (pinfunction "E_E") (pintype "passive"))
    )
    (net (code "185") (name "UC_5V") (class "Default")
      (node (ref "C39") (pin "1") (pinfunction "P$1_1") (pintype "passive"))
      (node (ref "J19") (pin "4") (pinfunction "4_4") (pintype "passive"))
      (node (ref "J20") (pin "4") (pinfunction "4_4") (pintype "passive"))
      (node (ref "J21") (pin "4") (pinfunction "4_4") (pintype "passive"))
      (node (ref "J22") (pin "4") (pinfunction "4_4") (pintype "passive"))
      (node (ref "J23") (pin "1") (pinfunction "1_1") (pintype "passive"))
      (node (ref "J23") (pin "2") (pinfunction "2_2") (pintype "passive"))
      (node (ref "J23") (pin "3") (pinfunction "3_3") (pintype "passive"))
      (node (ref "J23") (pin "4") (pinfunction "4_4") (pintype "passive"))
      (node (ref "J23") (pin "5") (pinfunction "5_5") (pintype "passive"))
      (node (ref "J23") (pin "6") (pinfunction "6_6") (pintype "passive"))
      (node (ref "J23") (pin "7") (pinfunction "7_7") (pintype "passive"))
      (node (ref "J23") (pin "8") (pinfunction "8_8") (pintype "passive"))
      (node (ref "J27") (pin "1") (pinfunction "1_1") (pintype "passive"))
      (node (ref "J27") (pin "2") (pinfunction "2_2") (pintype "passive"))
      (node (ref "J27") (pin "3") (pinfunction "3_3") (pintype "passive"))
      (node (ref "J27") (pin "4") (pinfunction "4_4") (pintype "passive"))
      (node (ref "J27") (pin "5") (pinfunction "5_5") (pintype "passive"))
      (node (ref "J27") (pin "6") (pinfunction "6_6") (pintype "passive"))
      (node (ref "J27") (pin "7") (pinfunction "7_7") (pintype "passive"))
      (node (ref "J27") (pin "8") (pinfunction "8_8") (pintype "passive"))
      (node (ref "NRF8001") (pin "10") (pinfunction "10_10") (pintype "passive"))
      (node (ref "R27") (pin "2") (pinfunction "2_2") (pintype "passive"))
      (node (ref "R32") (pin "2") (pinfunction "2_2") (pintype "passive"))
      (node (ref "R38") (pin "2") (pinfunction "2_2") (pintype "passive"))
      (node (ref "R39") (pin "2") (pinfunction "2_2") (pintype "passive"))
      (node (ref "U$1") (pin "5V0") (pinfunction "5V0_5V0") (pintype "bidirectional"))
      (node (ref "U2") (pin "28") (pinfunction "VDD_28") (pintype "power_in"))
      (node (ref "U8") (pin "1") (pinfunction "IN_1") (pintype "power_in"))
      (node (ref "U8") (pin "3") (pinfunction "EN_3") (pintype "input"))
    )
    (net (code "186") (name "US1_D1") (class "Default")
      (node (ref "J19") (pin "3") (pinfunction "3_3") (pintype "passive"))
    )
    (net (code "187") (name "US1_D2") (class "Default")
      (node (ref "J19") (pin "2") (pinfunction "2_2") (pintype "passive"))
    )
    (net (code "188") (name "US2_D1") (class "Default")
      (node (ref "J20") (pin "3") (pinfunction "3_3") (pintype "passive"))
    )
    (net (code "189") (name "US2_D2") (class "Default")
      (node (ref "J20") (pin "2") (pinfunction "2_2") (pintype "passive"))
    )
    (net (code "190") (name "US3_D1") (class "Default")
      (node (ref "J21") (pin "3") (pinfunction "3_3") (pintype "passive"))
    )
    (net (code "191") (name "US3_D2") (class "Default")
      (node (ref "J21") (pin "2") (pinfunction "2_2") (pintype "passive"))
    )
    (net (code "192") (name "US4_D1") (class "Default")
      (node (ref "J22") (pin "3") (pinfunction "3_3") (pintype "passive"))
    )
    (net (code "193") (name "US4_D2") (class "Default")
      (node (ref "J22") (pin "2") (pinfunction "2_2") (pintype "passive"))
    )
    (net (code "194") (name "VBACKUP") (class "Default")
      (node (ref "D34") (pin "C") (pinfunction "C_C") (pintype "passive"))
      (node (ref "U4") (pin "P$4") (pinfunction "VBACKUP_P$4") (pintype "bidirectional"))
    )
    (net (code "195") (name "VDD") (class "Default")
      (node (ref "C40") (pin "1") (pinfunction "P$1_1") (pintype "passive"))
      (node (ref "IC16") (pin "1") (pinfunction "VDDIO_1") (pintype "power_in"))
      (node (ref "IC16") (pin "22") (pinfunction "VDD_22") (pintype "power_in"))
      (node (ref "IC16") (pin "23") (pinfunction "VDD_23") (pintype "power_in"))
      (node (ref "IC16") (pin "3") (pinfunction "VDDIO_3") (pintype "power_in"))
      (node (ref "Q3") (pin "1") (pinfunction "G_1") (pintype "bidirectional"))
      (node (ref "Q4") (pin "1") (pinfunction "G_1") (pintype "bidirectional"))
      (node (ref "R36") (pin "2") (pinfunction "2_2") (pintype "passive"))
      (node (ref "R37") (pin "2") (pinfunction "2_2") (pintype "passive"))
      (node (ref "R40") (pin "2") (pinfunction "2_2") (pintype "passive"))
      (node (ref "R41") (pin "1") (pinfunction "1_1") (pintype "passive"))
      (node (ref "R42") (pin "1") (pinfunction "1_1") (pintype "passive"))
      (node (ref "R43") (pin "1") (pinfunction "1_1") (pintype "passive"))
      (node (ref "R44") (pin "1") (pinfunction "1_1") (pintype "passive"))
      (node (ref "U8") (pin "5") (pinfunction "OUT_5") (pintype "power_in"))
    )
    (net (code "196") (name "VIN") (class "Default")
      (node (ref "C11") (pin "2") (pinfunction "2_2") (pintype "passive"))
      (node (ref "C13") (pin "2") (pinfunction "2_2") (pintype "passive"))
      (node (ref "C14") (pin "+") (pinfunction "+_+") (pintype "passive"))
      (node (ref "C17") (pin "2") (pinfunction "2_2") (pintype "passive"))
      (node (ref "C19") (pin "+") (pinfunction "+_+") (pintype "passive"))
      (node (ref "C21") (pin "2") (pinfunction "2_2") (pintype "passive"))
      (node (ref "C22") (pin "2") (pinfunction "2_2") (pintype "passive"))
      (node (ref "C23") (pin "+") (pinfunction "+_+") (pintype "passive"))
      (node (ref "C25") (pin "2") (pinfunction "2_2") (pintype "passive"))
      (node (ref "C26") (pin "+") (pinfunction "+_+") (pintype "passive"))
      (node (ref "C28") (pin "2") (pinfunction "2_2") (pintype "passive"))
      (node (ref "C29") (pin "+") (pinfunction "+_+") (pintype "passive"))
      (node (ref "C31") (pin "2") (pinfunction "2_2") (pintype "passive"))
      (node (ref "C32") (pin "+") (pinfunction "+_+") (pintype "passive"))
      (node (ref "C34") (pin "2") (pinfunction "2_2") (pintype "passive"))
      (node (ref "D10") (pin "C") (pinfunction "C_C") (pintype "passive"))
      (node (ref "D11") (pin "C") (pinfunction "C_C") (pintype "passive"))
      (node (ref "D12") (pin "C") (pinfunction "C_C") (pintype "passive"))
      (node (ref "D13") (pin "C") (pinfunction "C_C") (pintype "passive"))
      (node (ref "D14") (pin "C") (pinfunction "C_C") (pintype "passive"))
      (node (ref "D21") (pin "C") (pinfunction "C_C") (pintype "passive"))
      (node (ref "D22") (pin "C") (pinfunction "C_C") (pintype "passive"))
      (node (ref "D23") (pin "C") (pinfunction "C_C") (pintype "passive"))
      (node (ref "D24") (pin "C") (pinfunction "C_C") (pintype "passive"))
      (node (ref "D7") (pin "C") (pinfunction "C_C") (pintype "passive"))
      (node (ref "D8") (pin "C") (pinfunction "C_C") (pintype "passive"))
      (node (ref "D9") (pin "C") (pinfunction "C_C") (pintype "passive"))
      (node (ref "IC10") (pin "1") (pinfunction "VI_1") (pintype "input"))
      (node (ref "IC11") (pin "1") (pinfunction "VIN_1") (pintype "input"))
      (node (ref "IC12") (pin "1") (pinfunction "VIN_1") (pintype "input"))
      (node (ref "IC13") (pin "1") (pinfunction "VIN_1") (pintype "input"))
      (node (ref "IC14") (pin "1") (pinfunction "VIN_1") (pintype "input"))
      (node (ref "IC15") (pin "1") (pinfunction "VI_1") (pintype "input"))
      (node (ref "IC2") (pin "4") (pinfunction "VS_4") (pintype "power_in"))
      (node (ref "IC4") (pin "4") (pinfunction "VS_4") (pintype "power_in"))
      (node (ref "IC5") (pin "1") (pinfunction "VI_1") (pintype "input"))
      (node (ref "IC6") (pin "1") (pinfunction "VI_1") (pintype "input"))
      (node (ref "IC7") (pin "1") (pinfunction "VIN_1") (pintype "input"))
      (node (ref "IC8") (pin "1") (pinfunction "VIN_1") (pintype "input"))
      (node (ref "IC9") (pin "4") (pinfunction "VS_4") (pintype "power_in"))
      (node (ref "U$14") (pin "+") (pinfunction "VCC_+") (pintype "bidirectional"))
    )
    (net (code "197") (name "WIFI_RX") (class "Default")
      (node (ref "J2") (pin "2") (pinfunction "2_2") (pintype "passive"))
      (node (ref "U3") (pin "RX") (pinfunction "RX_RX") (pintype "bidirectional"))
    )
    (net (code "198") (name "WIFI_TX") (class "Default")
      (node (ref "J2") (pin "1") (pinfunction "1_1") (pintype "passive"))
      (node (ref "U3") (pin "TX") (pinfunction "TX_TX") (pintype "bidirectional"))
    )
    (net (code "199") (name "unconnected-(IC1-ENABLE_A-Pad8)") (class "Default")
      (node (ref "IC1") (pin "8") (pinfunction "ENABLE_A_8") (pintype "bidirectional"))
    )
    (net (code "200") (name "unconnected-(IC1-ENABLE_B-Pad14)") (class "Default")
      (node (ref "IC1") (pin "14") (pinfunction "ENABLE_B_14") (pintype "bidirectional"))
    )
    (net (code "201") (name "unconnected-(IC1-GND_1-Pad1)") (class "Default")
      (node (ref "IC1") (pin "1") (pinfunction "GND_1_1") (pintype "bidirectional"))
    )
    (net (code "202") (name "unconnected-(IC1-GND_2-Pad10)") (class "Default")
      (node (ref "IC1") (pin "10") (pinfunction "GND_2_10") (pintype "bidirectional"))
    )
    (net (code "203") (name "unconnected-(IC1-GND_3-Pad11)") (class "Default")
      (node (ref "IC1") (pin "11") (pinfunction "GND_3_11") (pintype "bidirectional"))
    )
    (net (code "204") (name "unconnected-(IC1-GND_4-Pad20)") (class "Default")
      (node (ref "IC1") (pin "20") (pinfunction "GND_4_20") (pintype "bidirectional"))
    )
    (net (code "205") (name "unconnected-(IC1-INPUT1-Pad7)") (class "Default")
      (node (ref "IC1") (pin "7") (pinfunction "INPUT1_7") (pintype "bidirectional"))
    )
    (net (code "206") (name "unconnected-(IC1-INPUT_2-Pad9)") (class "Default")
      (node (ref "IC1") (pin "9") (pinfunction "INPUT_2_9") (pintype "bidirectional"))
    )
    (net (code "207") (name "unconnected-(IC1-INPUT_3-Pad13)") (class "Default")
      (node (ref "IC1") (pin "13") (pinfunction "INPUT_3_13") (pintype "bidirectional"))
    )
    (net (code "208") (name "unconnected-(IC1-INPUT_4-Pad15)") (class "Default")
      (node (ref "IC1") (pin "15") (pinfunction "INPUT_4_15") (pintype "bidirectional"))
    )
    (net (code "209") (name "unconnected-(IC1-N.C._1-Pad3)") (class "Default")
      (node (ref "IC1") (pin "3") (pinfunction "N.C._1_3") (pintype "bidirectional"))
    )
    (net (code "210") (name "unconnected-(IC1-N.C._2-Pad18)") (class "Default")
      (node (ref "IC1") (pin "18") (pinfunction "N.C._2_18") (pintype "bidirectional"))
    )
    (net (code "211") (name "unconnected-(IC1-OUT_1-Pad4)") (class "Default")
      (node (ref "IC1") (pin "4") (pinfunction "OUT_1_4") (pintype "bidirectional"))
    )
    (net (code "212") (name "unconnected-(IC1-OUT_2-Pad5)") (class "Default")
      (node (ref "IC1") (pin "5") (pinfunction "OUT_2_5") (pintype "bidirectional"))
    )
    (net (code "213") (name "unconnected-(IC1-OUT_3-Pad16)") (class "Default")
      (node (ref "IC1") (pin "16") (pinfunction "OUT_3_16") (pintype "bidirectional"))
    )
    (net (code "214") (name "unconnected-(IC1-OUT_4-Pad17)") (class "Default")
      (node (ref "IC1") (pin "17") (pinfunction "OUT_4_17") (pintype "bidirectional"))
    )
    (net (code "215") (name "unconnected-(IC1-SENSE_A-Pad2)") (class "Default")
      (node (ref "IC1") (pin "2") (pinfunction "SENSE_A_2") (pintype "bidirectional"))
    )
    (net (code "216") (name "unconnected-(IC1-SENSE_B-Pad19)") (class "Default")
      (node (ref "IC1") (pin "19") (pinfunction "SENSE_B_19") (pintype "bidirectional"))
    )
    (net (code "217") (name "unconnected-(IC1-VS-Pad6)") (class "Default")
      (node (ref "IC1") (pin "6") (pinfunction "VS_6") (pintype "bidirectional"))
    )
    (net (code "218") (name "unconnected-(IC1-VSS-Pad12)") (class "Default")
      (node (ref "IC1") (pin "12") (pinfunction "VSS_12") (pintype "bidirectional"))
    )
    (net (code "219") (name "unconnected-(NRF8001-Pad6)") (class "Default")
      (node (ref "NRF8001") (pin "6") (pinfunction "6_6") (pintype "passive"))
    )
    (net (code "220") (name "unconnected-(NRF8001-Pad8)") (class "Default")
      (node (ref "NRF8001") (pin "8") (pinfunction "8_8") (pintype "passive"))
    )
    (net (code "221") (name "unconnected-(S2-PadO)") (class "Default")
      (node (ref "S2") (pin "O") (pinfunction "O_O") (pintype "passive"))
    )
    (net (code "222") (name "unconnected-(STEPDRV2-MS1-Pad2)") (class "Default")
      (node (ref "STEPDRV2") (pin "2") (pinfunction "MS1_2") (pintype "input"))
    )
    (net (code "223") (name "unconnected-(STEPDRV2-MS2-Pad3)") (class "Default")
      (node (ref "STEPDRV2") (pin "3") (pinfunction "MS2_3") (pintype "input"))
    )
    (net (code "224") (name "unconnected-(STEPDRV2-MS3-Pad4)") (class "Default")
      (node (ref "STEPDRV2") (pin "4") (pinfunction "MS3_4") (pintype "input"))
    )
    (net (code "225") (name "unconnected-(U$1-AREF(IO42)-PadAREF)") (class "Default")
      (node (ref "U$1") (pin "AREF") (pinfunction "AREF(IO42)_AREF") (pintype "bidirectional"))
    )
    (net (code "226") (name "unconnected-(U$1-IO40\\-PadIO40)") (class "Default")
      (node (ref "U$1") (pin "IO40") (pinfunction "IO40\\_IO40") (pintype "bidirectional"))
    )
    (net (code "227") (name "unconnected-(U$1-Pad3V3)") (class "Default")
      (node (ref "U$1") (pin "3V3") (pinfunction "3V3_3V3") (pintype "bidirectional"))
    )
    (net (code "228") (name "unconnected-(U$1-PadGND3)") (class "Default")
      (node (ref "U$1") (pin "GND3") (pinfunction "GND3_GND3") (pintype "bidirectional"))
    )
    (net (code "229") (name "unconnected-(U$1-PadIO38)") (class "Default")
      (node (ref "U$1") (pin "IO38") (pinfunction "IO38_IO38") (pintype "bidirectional"))
    )
    (net (code "230") (name "unconnected-(U$1-PadIO39)") (class "Default")
      (node (ref "U$1") (pin "IO39") (pinfunction "IO39_IO39") (pintype "bidirectional"))
    )
    (net (code "231") (name "unconnected-(U$1-PadIO41)") (class "Default")
      (node (ref "U$1") (pin "IO41") (pinfunction "IO41_IO41") (pintype "bidirectional"))
    )
    (net (code "232") (name "unconnected-(U$1-PadIOREF)") (class "Default")
      (node (ref "U$1") (pin "IOREF") (pinfunction "IOREF_IOREF") (pintype "bidirectional"))
    )
    (net (code "233") (name "unconnected-(U$1-PadVIN)") (class "Default")
      (node (ref "U$1") (pin "VIN") (pinfunction "VIN_VIN") (pintype "bidirectional"))
    )
    (net (code "234") (name "unconnected-(U$1-PadV_N)") (class "Default")
      (node (ref "U$1") (pin "V_N") (pinfunction "V_N_V_N") (pintype "bidirectional"))
    )
    (net (code "235") (name "unconnected-(U$1-PadV_P)") (class "Default")
      (node (ref "U$1") (pin "V_P") (pinfunction "V_P_V_P") (pintype "bidirectional"))
    )
    (net (code "236") (name "unconnected-(U$1-RESET-PadRST)") (class "Default")
      (node (ref "U$1") (pin "RST") (pinfunction "RESET_RST") (pintype "bidirectional"))
    )
    (net (code "237") (name "unconnected-(U4-NC-PadP$6)") (class "Default")
      (node (ref "U4") (pin "P$6") (pinfunction "NC_P$6") (pintype "bidirectional"))
    )
    (net (code "238") (name "unconnected-(U4-NC-PadP$7)") (class "Default")
      (node (ref "U4") (pin "P$7") (pinfunction "NC_P$7") (pintype "bidirectional"))
    )
    (net (code "239") (name "unconnected-(U4-NC-PadP$15)") (class "Default")
      (node (ref "U4") (pin "P$15") (pinfunction "NC_P$15") (pintype "bidirectional"))
    )
    (net (code "240") (name "unconnected-(U4-NC-PadP$16)") (class "Default")
      (node (ref "U4") (pin "P$16") (pinfunction "NC_P$16") (pintype "bidirectional"))
    )
    (net (code "241") (name "unconnected-(U4-NC-PadP$17)") (class "Default")
      (node (ref "U4") (pin "P$17") (pinfunction "NC_P$17") (pintype "bidirectional"))
    )
    (net (code "242") (name "unconnected-(U4-NC-PadP$18)") (class "Default")
      (node (ref "U4") (pin "P$18") (pinfunction "NC_P$18") (pintype "bidirectional"))
    )
    (net (code "243") (name "unconnected-(U4-NC-PadP$20)") (class "Default")
      (node (ref "U4") (pin "P$20") (pinfunction "NC_P$20") (pintype "bidirectional"))
    )
    (net (code "244") (name "unconnected-(U4-NRESET-PadP$2)") (class "Default")
      (node (ref "U4") (pin "P$2") (pinfunction "NRESET_P$2") (pintype "bidirectional"))
    )
    (net (code "245") (name "unconnected-(U4-RTCM-PadP$14)") (class "Default")
      (node (ref "U4") (pin "P$14") (pinfunction "RTCM_P$14") (pintype "bidirectional"))
    )
    (net (code "246") (name "unconnected-(U5-P4-Pad4)") (class "Default")
      (node (ref "U5") (pin "4") (pinfunction "P4_4") (pintype "bidirectional"))
    )
    (net (code "247") (name "unconnected-(U8-P4-Pad4)") (class "Default")
      (node (ref "U8") (pin "4") (pinfunction "P4_4") (pintype "bidirectional"))
    )
  )
)
